# US_EPS_LM.net
KiCad netlist of a schematic drawn in Altium Designer
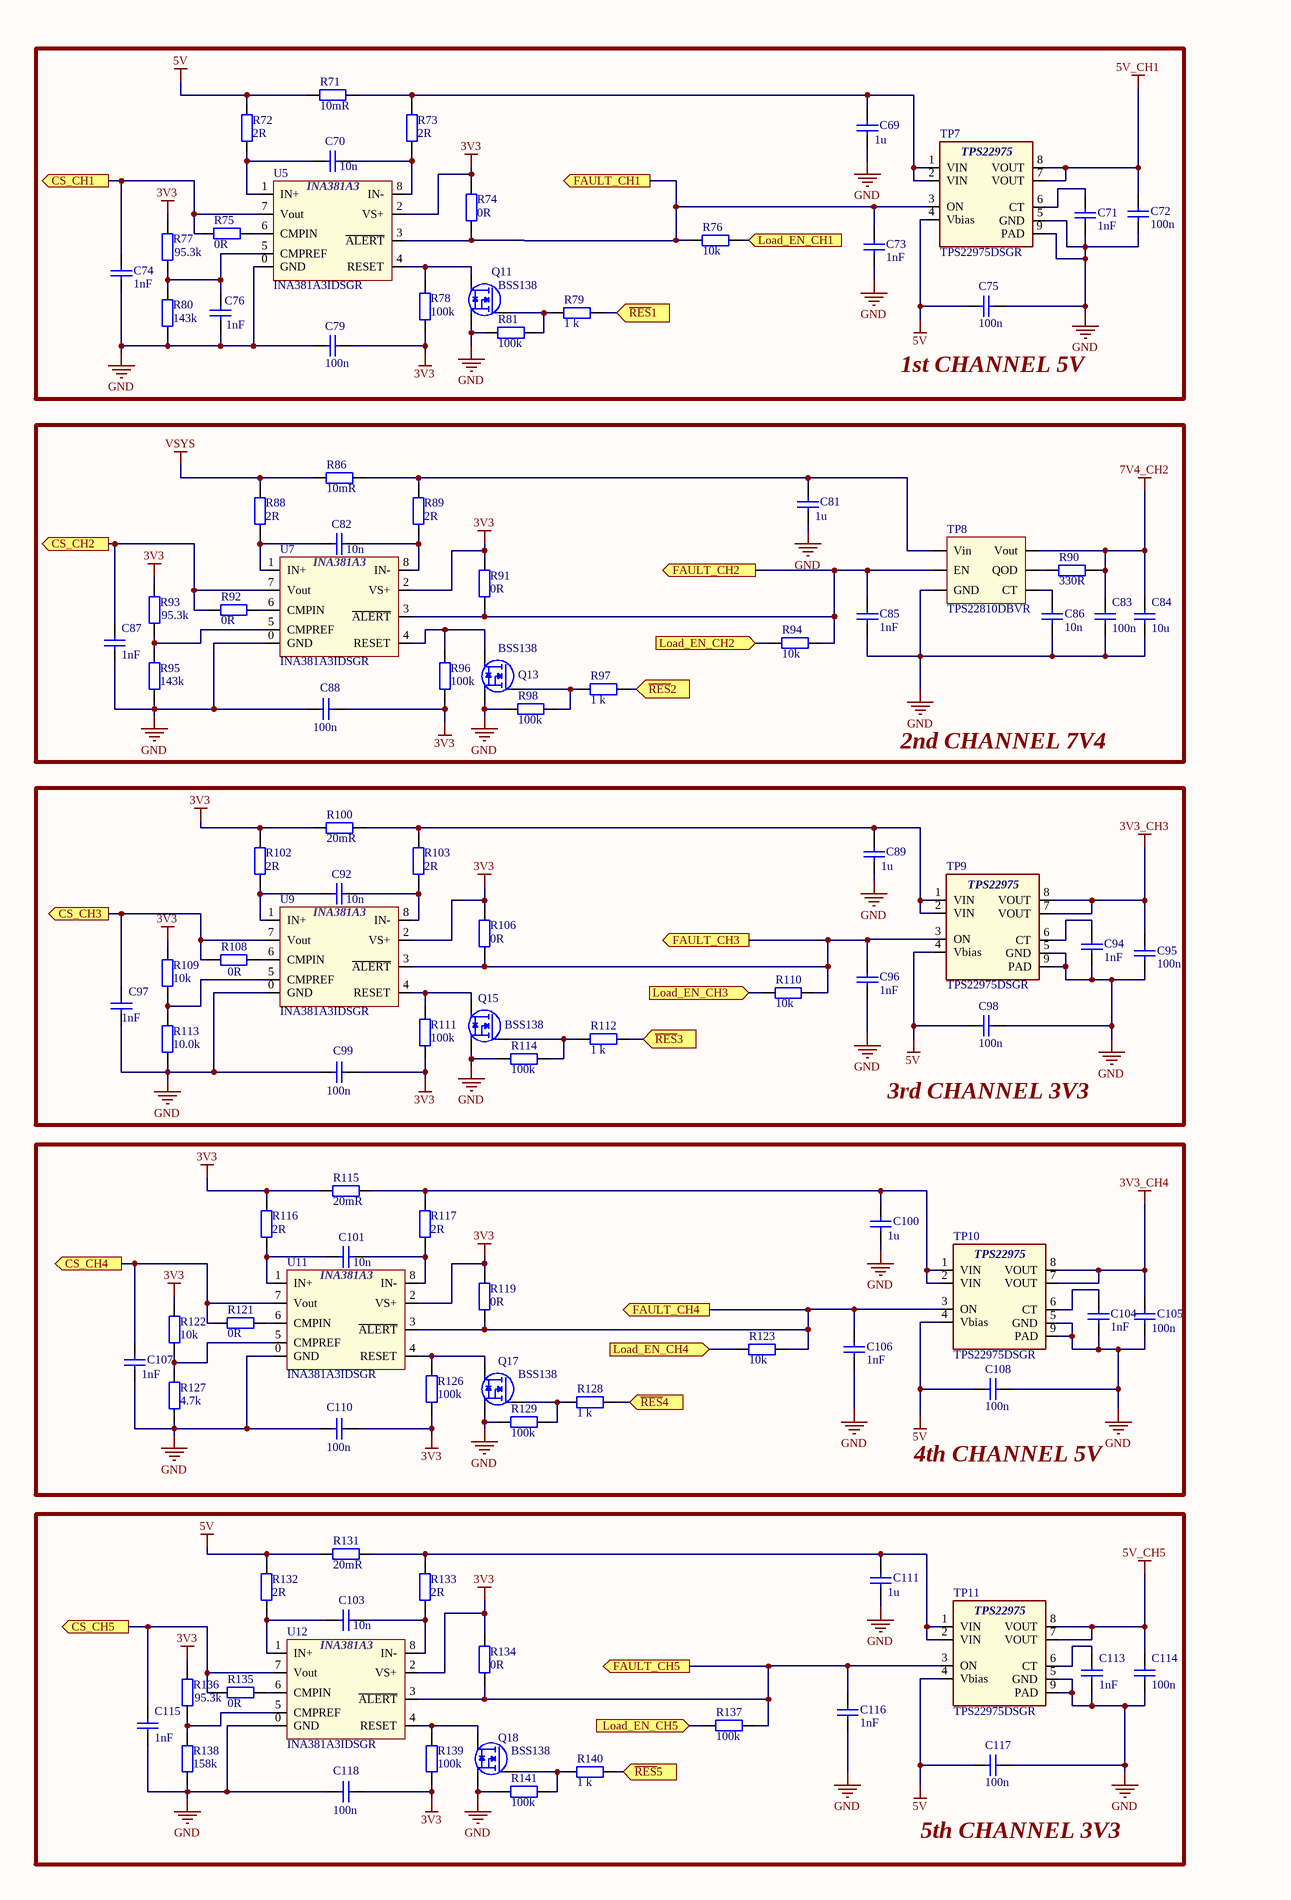
[diagram p0: US_EPS_LM.SchDoc, left]
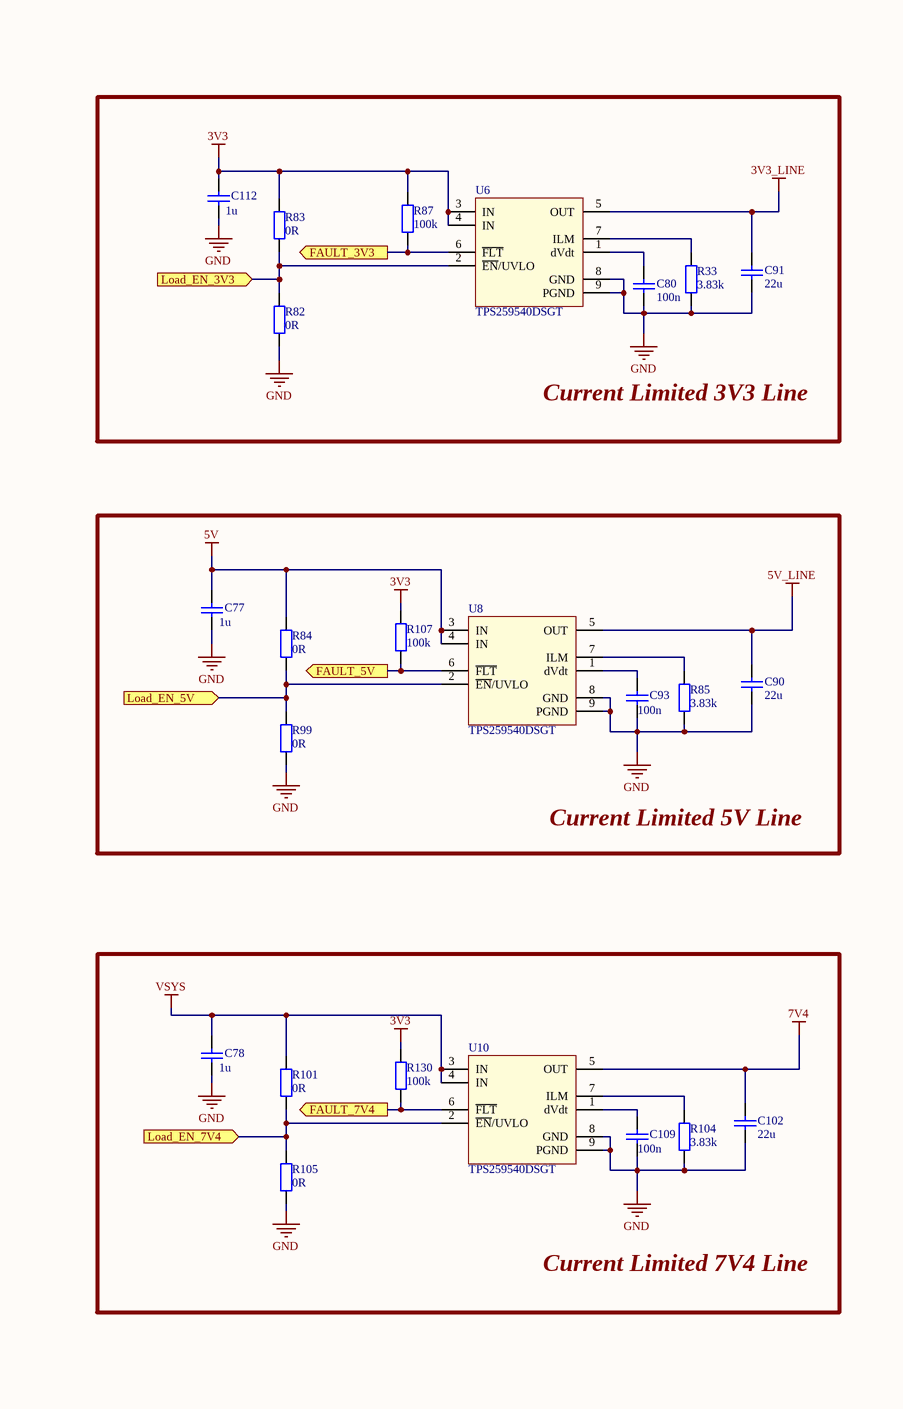
[diagram p1: US_EPS_LM.SchDoc, right]

(export (version "E")
  (design (tool "Eeschema 10.0.6"))
  (components
    (comp (ref "C69")
      (value "1u")
      (footprint "C0603_IPC_HD")
      (description "CAP CER 1UF 16V X7R 0603")
      (fields
        (field (name "MANUFACTURER") "Samsung Electro-Mechanics")
        (field (name "MANUFACTURER PART NUMBER") "CL10B105MO8NNWC")
      )
      (libsource (lib "alfasat_lib") (part "CL10B105MO8NNWC"))
    )
    (comp (ref "C70")
      (value "10n")
      (footprint "C0603_IPC_HD")
      (description "CAP CER 0.01UF 50V X7R 0603")
      (fields
        (field (name "MANUFACTURER") "Samsung Electro-Mechanics")
        (field (name "MANUFACTURER PART NUMBER") "CL10B103KB8NNNC")
      )
      (libsource (lib "alfasat_lib") (part "CL10B103KB8NNNC"))
    )
    (comp (ref "C71")
      (value "1nF")
      (footprint "C0603_IPC_HD")
      (description "CAP CER 1000PF 50V X7R 0603")
      (fields
        (field (name "MANUFACTURER") "Samsung Electro-Mechanics")
        (field (name "MANUFACTURER PART NUMBER") "CL10B102KB8NNNC")
      )
      (libsource (lib "alfasat_lib_eps") (part "CL0603_1nF_0603"))
    )
    (comp (ref "C72")
      (value "100n")
      (footprint "C0603_IPC_HD")
      (description "CAP CER 0.1UF 16V X7R 0603")
      (fields
        (field (name "MANUFACTURER") "Samsung Electro-Mechanics")
        (field (name "MANUFACTURER PART NUMBER") "CL10B104KO8NNNC")
      )
      (libsource (lib "alfasat_lib") (part "CL10B104KO8NNNC"))
    )
    (comp (ref "C73")
      (value "1nF")
      (footprint "C0603_IPC_HD")
      (description "CAP CER 1000PF 50V X7R 0603")
      (fields
        (field (name "MANUFACTURER") "Samsung Electro-Mechanics")
        (field (name "MANUFACTURER PART NUMBER") "CL10B102KB8NNNC")
      )
      (libsource (lib "alfasat_lib_eps") (part "CL0603_1nF_0603"))
    )
    (comp (ref "C74")
      (value "1nF")
      (footprint "C0603_IPC_HD")
      (description "CAP CER 1000PF 50V X7R 0603")
      (fields
        (field (name "MANUFACTURER") "Samsung Electro-Mechanics")
        (field (name "MANUFACTURER PART NUMBER") "CL10B102KB8NNNC")
      )
      (libsource (lib "alfasat_lib_eps") (part "CL0603_1nF_0603"))
    )
    (comp (ref "C75")
      (value "100n")
      (footprint "C0603_IPC_HD")
      (description "CAP CER 0.1UF 16V X7R 0603")
      (fields
        (field (name "MANUFACTURER") "Samsung Electro-Mechanics")
        (field (name "MANUFACTURER PART NUMBER") "CL10B104KO8NNNC")
      )
      (libsource (lib "alfasat_lib") (part "CL10B104KO8NNNC"))
    )
    (comp (ref "C76")
      (value "1nF")
      (footprint "C0603_IPC_HD")
      (description "CAP CER 1000PF 50V X7R 0603")
      (fields
        (field (name "MANUFACTURER") "Samsung Electro-Mechanics")
        (field (name "MANUFACTURER PART NUMBER") "CL10B102KB8NNNC")
      )
      (libsource (lib "alfasat_lib_eps") (part "CL0603_1nF_0603"))
    )
    (comp (ref "C77")
      (value "1u")
      (footprint "C0603_IPC_HD")
      (description "CAP CER 1UF 16V X7R 0603")
      (fields
        (field (name "MANUFACTURER") "Samsung Electro-Mechanics")
        (field (name "MANUFACTURER PART NUMBER") "CL10B105MO8NNWC")
      )
      (libsource (lib "alfasat_parts_lib") (part "CL10B105MO8NNWC"))
    )
    (comp (ref "C78")
      (value "1u")
      (footprint "C0603_IPC_HD")
      (description "CAP CER 1UF 16V X7R 0603")
      (fields
        (field (name "MANUFACTURER") "Samsung Electro-Mechanics")
        (field (name "MANUFACTURER PART NUMBER") "CL10B105MO8NNWC")
      )
      (libsource (lib "alfasat_parts_lib") (part "CL10B105MO8NNWC"))
    )
    (comp (ref "C79")
      (value "100n")
      (footprint "C0603_IPC_HD")
      (description "CAP CER 0.1UF 16V X7R 0603")
      (fields
        (field (name "MANUFACTURER") "Samsung Electro-Mechanics")
        (field (name "MANUFACTURER PART NUMBER") "CL10B104KO8NNNC")
      )
      (libsource (lib "alfasat_lib") (part "CL10B104KO8NNNC"))
    )
    (comp (ref "C80")
      (value "100n")
      (footprint "C0603_IPC_HD")
      (description "CAP CER 0.1UF 16V X7R 0603")
      (fields
        (field (name "MANUFACTURER") "Samsung Electro-Mechanics")
        (field (name "MANUFACTURER PART NUMBER") "CL10B104KO8NNNC")
      )
      (libsource (lib "alfasat_lib") (part "CL10B104KO8NNNC"))
    )
    (comp (ref "C81")
      (value "1u")
      (footprint "C0603_IPC_HD")
      (description "CAP CER 1UF 16V X7R 0603")
      (fields
        (field (name "MANUFACTURER") "Samsung Electro-Mechanics")
        (field (name "MANUFACTURER PART NUMBER") "CL10B105MO8NNWC")
      )
      (libsource (lib "alfasat_lib") (part "CL10B105MO8NNWC"))
    )
    (comp (ref "C82")
      (value "10n")
      (footprint "C0603_IPC_HD")
      (description "CAP CER 0.01UF 50V X7R 0603")
      (fields
        (field (name "MANUFACTURER") "Samsung Electro-Mechanics")
        (field (name "MANUFACTURER PART NUMBER") "CL10B103KB8NNNC")
      )
      (libsource (lib "alfasat_lib") (part "CL10B103KB8NNNC"))
    )
    (comp (ref "C83")
      (value "100n")
      (footprint "C0603_IPC_HD")
      (description "CAP CER 0.1UF 16V X7R 0603")
      (fields
        (field (name "MANUFACTURER") "Samsung Electro-Mechanics")
        (field (name "MANUFACTURER PART NUMBER") "CL10B104KO8NNNC")
      )
      (libsource (lib "alfasat_lib") (part "CL10B104KO8NNNC"))
    )
    (comp (ref "C84")
      (value "10u")
      (footprint "C0805_IPC_HD")
      (description "CAP CER 10UF 16V X7R 0805")
      (fields
        (field (name "MANUFACTURER") "Samsung Electro-Mechanics")
        (field (name "MANUFACTURER PART NUMBER") "CL21B106KOQNNNG")
      )
      (libsource (lib "alfasat_lib") (part "CL21B106KOQNNNG"))
    )
    (comp (ref "C85")
      (value "1nF")
      (footprint "C0603_IPC_HD")
      (description "CAP CER 1000PF 50V X7R 0603")
      (fields
        (field (name "MANUFACTURER") "Samsung Electro-Mechanics")
        (field (name "MANUFACTURER PART NUMBER") "CL10B102KB8NNNC")
      )
      (libsource (lib "alfasat_lib_eps") (part "CL0603_1nF_0603"))
    )
    (comp (ref "C86")
      (value "10n")
      (footprint "C0603_IPC_HD")
      (description "CAP CER 0.01UF 50V X7R 0603")
      (fields
        (field (name "MANUFACTURER") "Samsung Electro-Mechanics")
        (field (name "MANUFACTURER PART NUMBER") "CL10B103KB8NNNC")
      )
      (libsource (lib "alfasat_lib") (part "CL10B103KB8NNNC"))
    )
    (comp (ref "C87")
      (value "1nF")
      (footprint "C0603_IPC_HD")
      (description "CAP CER 1000PF 50V X7R 0603")
      (fields
        (field (name "MANUFACTURER") "Samsung Electro-Mechanics")
        (field (name "MANUFACTURER PART NUMBER") "CL10B102KB8NNNC")
      )
      (libsource (lib "alfasat_lib_eps") (part "CL0603_1nF_0603"))
    )
    (comp (ref "C88")
      (value "100n")
      (footprint "C0603_IPC_HD")
      (description "CAP CER 0.1UF 16V X7R 0603")
      (fields
        (field (name "MANUFACTURER") "Samsung Electro-Mechanics")
        (field (name "MANUFACTURER PART NUMBER") "CL10B104KO8NNNC")
      )
      (libsource (lib "alfasat_lib") (part "CL10B104KO8NNNC"))
    )
    (comp (ref "C89")
      (value "1u")
      (footprint "C0603_IPC_HD")
      (description "CAP CER 1UF 16V X7R 0603")
      (fields
        (field (name "MANUFACTURER") "Samsung Electro-Mechanics")
        (field (name "MANUFACTURER PART NUMBER") "CL10B105MO8NNWC")
      )
      (libsource (lib "alfasat_lib") (part "CL10B105MO8NNWC"))
    )
    (comp (ref "C90")
      (value "22u")
      (footprint "C0805_IPC_HD")
      (description "CAP CER 22UF 16V X5R 0805")
      (fields
        (field (name "MANUFACTURER") "Samsung Electro-Mechanics")
        (field (name "MANUFACTURER PART NUMBER") "CL21A226MOCLRNC")
      )
      (libsource (lib "alfasat_parts_lib") (part "CL21A226MOCLRNC"))
    )
    (comp (ref "C91")
      (value "22u")
      (footprint "C0805_IPC_HD")
      (description "CAP CER 22UF 16V X5R 0805")
      (fields
        (field (name "MANUFACTURER") "Samsung Electro-Mechanics")
        (field (name "MANUFACTURER PART NUMBER") "CL21A226MOCLRNC")
      )
      (libsource (lib "alfasat_parts_lib") (part "CL21A226MOCLRNC"))
    )
    (comp (ref "C92")
      (value "10n")
      (footprint "C0603_IPC_HD")
      (description "CAP CER 0.01UF 50V X7R 0603")
      (fields
        (field (name "MANUFACTURER") "Samsung Electro-Mechanics")
        (field (name "MANUFACTURER PART NUMBER") "CL10B103KB8NNNC")
      )
      (libsource (lib "alfasat_lib") (part "CL10B103KB8NNNC"))
    )
    (comp (ref "C93")
      (value "100n")
      (footprint "C0603_IPC_HD")
      (description "CAP CER 0.1UF 16V X7R 0603")
      (fields
        (field (name "MANUFACTURER") "Samsung Electro-Mechanics")
        (field (name "MANUFACTURER PART NUMBER") "CL10B104KO8NNNC")
      )
      (libsource (lib "alfasat_lib") (part "CL10B104KO8NNNC"))
    )
    (comp (ref "C94")
      (value "1nF")
      (footprint "C0603_IPC_HD")
      (description "CAP CER 1000PF 50V X7R 0603")
      (fields
        (field (name "MANUFACTURER") "Samsung Electro-Mechanics")
        (field (name "MANUFACTURER PART NUMBER") "CL10B102KB8NNNC")
      )
      (libsource (lib "alfasat_lib_eps") (part "CL0603_1nF_0603"))
    )
    (comp (ref "C95")
      (value "100n")
      (footprint "C0603_IPC_HD")
      (description "CAP CER 0.1UF 16V X7R 0603")
      (fields
        (field (name "MANUFACTURER") "Samsung Electro-Mechanics")
        (field (name "MANUFACTURER PART NUMBER") "CL10B104KO8NNNC")
      )
      (libsource (lib "alfasat_lib") (part "CL10B104KO8NNNC"))
    )
    (comp (ref "C96")
      (value "1nF")
      (footprint "C0603_IPC_HD")
      (description "CAP CER 1000PF 50V X7R 0603")
      (fields
        (field (name "MANUFACTURER") "Samsung Electro-Mechanics")
        (field (name "MANUFACTURER PART NUMBER") "CL10B102KB8NNNC")
      )
      (libsource (lib "alfasat_lib_eps") (part "CL0603_1nF_0603"))
    )
    (comp (ref "C97")
      (value "1nF")
      (footprint "C0603_IPC_HD")
      (description "CAP CER 1000PF 50V X7R 0603")
      (fields
        (field (name "MANUFACTURER") "Samsung Electro-Mechanics")
        (field (name "MANUFACTURER PART NUMBER") "CL10B102KB8NNNC")
      )
      (libsource (lib "alfasat_lib_eps") (part "CL0603_1nF_0603"))
    )
    (comp (ref "C98")
      (value "100n")
      (footprint "C0603_IPC_HD")
      (description "CAP CER 0.1UF 16V X7R 0603")
      (fields
        (field (name "MANUFACTURER") "Samsung Electro-Mechanics")
        (field (name "MANUFACTURER PART NUMBER") "CL10B104KO8NNNC")
      )
      (libsource (lib "alfasat_lib") (part "CL10B104KO8NNNC"))
    )
    (comp (ref "C99")
      (value "100n")
      (footprint "C0603_IPC_HD")
      (description "CAP CER 0.1UF 16V X7R 0603")
      (fields
        (field (name "MANUFACTURER") "Samsung Electro-Mechanics")
        (field (name "MANUFACTURER PART NUMBER") "CL10B104KO8NNNC")
      )
      (libsource (lib "alfasat_lib") (part "CL10B104KO8NNNC"))
    )
    (comp (ref "C100")
      (value "1u")
      (footprint "C0603_IPC_HD")
      (description "CAP CER 1UF 16V X7R 0603")
      (fields
        (field (name "MANUFACTURER") "Samsung Electro-Mechanics")
        (field (name "MANUFACTURER PART NUMBER") "CL10B105MO8NNWC")
      )
      (libsource (lib "alfasat_lib") (part "CL10B105MO8NNWC"))
    )
    (comp (ref "C101")
      (value "10n")
      (footprint "C0603_IPC_HD")
      (description "CAP CER 0.01UF 50V X7R 0603")
      (fields
        (field (name "MANUFACTURER") "Samsung Electro-Mechanics")
        (field (name "MANUFACTURER PART NUMBER") "CL10B103KB8NNNC")
      )
      (libsource (lib "alfasat_lib") (part "CL10B103KB8NNNC"))
    )
    (comp (ref "C102")
      (value "22u")
      (footprint "C0805_IPC_HD")
      (description "CAP CER 22UF 16V X5R 0805")
      (fields
        (field (name "MANUFACTURER") "Samsung Electro-Mechanics")
        (field (name "MANUFACTURER PART NUMBER") "CL21A226MOCLRNC")
      )
      (libsource (lib "alfasat_lib") (part "CL21A226MOCLRNC"))
    )
    (comp (ref "C103")
      (value "10n")
      (footprint "C0603_IPC_HD")
      (description "CAP CER 0.01UF 50V X7R 0603")
      (fields
        (field (name "MANUFACTURER") "Samsung Electro-Mechanics")
        (field (name "MANUFACTURER PART NUMBER") "CL10B103KB8NNNC")
      )
      (libsource (lib "alfasat_lib") (part "CL10B103KB8NNNC"))
    )
    (comp (ref "C104")
      (value "1nF")
      (footprint "C0603_IPC_HD")
      (description "CAP CER 1000PF 50V X7R 0603")
      (fields
        (field (name "MANUFACTURER") "Samsung Electro-Mechanics")
        (field (name "MANUFACTURER PART NUMBER") "CL10B102KB8NNNC")
      )
      (libsource (lib "alfasat_lib_eps") (part "CL0603_1nF_0603"))
    )
    (comp (ref "C105")
      (value "100n")
      (footprint "C0603_IPC_HD")
      (description "CAP CER 0.1UF 16V X7R 0603")
      (fields
        (field (name "MANUFACTURER") "Samsung Electro-Mechanics")
        (field (name "MANUFACTURER PART NUMBER") "CL10B104KO8NNNC")
      )
      (libsource (lib "alfasat_lib") (part "CL10B104KO8NNNC"))
    )
    (comp (ref "C106")
      (value "1nF")
      (footprint "C0603_IPC_HD")
      (description "CAP CER 1000PF 50V X7R 0603")
      (fields
        (field (name "MANUFACTURER") "Samsung Electro-Mechanics")
        (field (name "MANUFACTURER PART NUMBER") "CL10B102KB8NNNC")
      )
      (libsource (lib "alfasat_lib_eps") (part "CL0603_1nF_0603"))
    )
    (comp (ref "C107")
      (value "1nF")
      (footprint "C0603_IPC_HD")
      (description "CAP CER 1000PF 50V X7R 0603")
      (fields
        (field (name "MANUFACTURER") "Samsung Electro-Mechanics")
        (field (name "MANUFACTURER PART NUMBER") "CL10B102KB8NNNC")
      )
      (libsource (lib "alfasat_lib_eps") (part "CL0603_1nF_0603"))
    )
    (comp (ref "C108")
      (value "100n")
      (footprint "C0603_IPC_HD")
      (description "CAP CER 0.1UF 16V X7R 0603")
      (fields
        (field (name "MANUFACTURER") "Samsung Electro-Mechanics")
        (field (name "MANUFACTURER PART NUMBER") "CL10B104KO8NNNC")
      )
      (libsource (lib "alfasat_lib") (part "CL10B104KO8NNNC"))
    )
    (comp (ref "C109")
      (value "100n")
      (footprint "C0603_IPC_HD")
      (description "CAP CER 0.1UF 16V X7R 0603")
      (fields
        (field (name "MANUFACTURER") "Samsung Electro-Mechanics")
        (field (name "MANUFACTURER PART NUMBER") "CL10B104KO8NNNC")
      )
      (libsource (lib "alfasat_lib") (part "CL10B104KO8NNNC"))
    )
    (comp (ref "C110")
      (value "100n")
      (footprint "C0603_IPC_HD")
      (description "CAP CER 0.1UF 16V X7R 0603")
      (fields
        (field (name "MANUFACTURER") "Samsung Electro-Mechanics")
        (field (name "MANUFACTURER PART NUMBER") "CL10B104KO8NNNC")
      )
      (libsource (lib "alfasat_lib") (part "CL10B104KO8NNNC"))
    )
    (comp (ref "C111")
      (value "1u")
      (footprint "C0603_IPC_HD")
      (description "CAP CER 1UF 16V X7R 0603")
      (fields
        (field (name "MANUFACTURER") "Samsung Electro-Mechanics")
        (field (name "MANUFACTURER PART NUMBER") "CL10B105MO8NNWC")
      )
      (libsource (lib "alfasat_lib") (part "CL10B105MO8NNWC"))
    )
    (comp (ref "C112")
      (value "1u")
      (footprint "C0603_IPC_HD")
      (description "CAP CER 1UF 16V X7R 0603")
      (fields
        (field (name "MANUFACTURER") "Samsung Electro-Mechanics")
        (field (name "MANUFACTURER PART NUMBER") "CL10B105MO8NNWC")
      )
      (libsource (lib "alfasat_parts_lib") (part "CL10B105MO8NNWC"))
    )
    (comp (ref "C113")
      (value "1nF")
      (footprint "C0603_IPC_HD")
      (description "CAP CER 1000PF 50V X7R 0603")
      (fields
        (field (name "MANUFACTURER") "Samsung Electro-Mechanics")
        (field (name "MANUFACTURER PART NUMBER") "CL10B102KB8NNNC")
      )
      (libsource (lib "alfasat_lib_eps") (part "CL0603_1nF_0603"))
    )
    (comp (ref "C114")
      (value "100n")
      (footprint "C0603_IPC_HD")
      (description "CAP CER 0.1UF 16V X7R 0603")
      (fields
        (field (name "MANUFACTURER") "Samsung Electro-Mechanics")
        (field (name "MANUFACTURER PART NUMBER") "CL10B104KO8NNNC")
      )
      (libsource (lib "alfasat_lib") (part "CL10B104KO8NNNC"))
    )
    (comp (ref "C115")
      (value "1nF")
      (footprint "C0603_IPC_HD")
      (description "CAP CER 1000PF 50V X7R 0603")
      (fields
        (field (name "MANUFACTURER") "Samsung Electro-Mechanics")
        (field (name "MANUFACTURER PART NUMBER") "CL10B102KB8NNNC")
      )
      (libsource (lib "alfasat_lib_eps") (part "CL0603_1nF_0603"))
    )
    (comp (ref "C116")
      (value "1nF")
      (footprint "C0603_IPC_HD")
      (description "CAP CER 1000PF 50V X7R 0603")
      (fields
        (field (name "MANUFACTURER") "Samsung Electro-Mechanics")
        (field (name "MANUFACTURER PART NUMBER") "CL10B102KB8NNNC")
      )
      (libsource (lib "alfasat_lib_eps") (part "CL0603_1nF_0603"))
    )
    (comp (ref "C117")
      (value "100n")
      (footprint "C0603_IPC_HD")
      (description "CAP CER 0.1UF 16V X7R 0603")
      (fields
        (field (name "MANUFACTURER") "Samsung Electro-Mechanics")
        (field (name "MANUFACTURER PART NUMBER") "CL10B104KO8NNNC")
      )
      (libsource (lib "alfasat_lib") (part "CL10B104KO8NNNC"))
    )
    (comp (ref "C118")
      (value "100n")
      (footprint "C0603_IPC_HD")
      (description "CAP CER 0.1UF 16V X7R 0603")
      (fields
        (field (name "MANUFACTURER") "Samsung Electro-Mechanics")
        (field (name "MANUFACTURER PART NUMBER") "CL10B104KO8NNNC")
      )
      (libsource (lib "alfasat_lib") (part "CL10B104KO8NNNC"))
    )
    (comp (ref "Q11")
      (value "BSS138")
      (footprint "SOT23")
      (description "N-Channel Logic Level Enhancement Mode Field Effect Transistor")
      (fields (field (name "MANUFACTURER") "Diodes Incorporated"))
      (libsource (lib "alfasat_lib") (part "BSS138"))
    )
    (comp (ref "Q13")
      (value "BSS138")
      (footprint "SOT23")
      (description "N-Channel Logic Level Enhancement Mode Field Effect Transistor")
      (fields (field (name "MANUFACTURER") "Diodes Incorporated"))
      (libsource (lib "alfasat_lib") (part "BSS138"))
    )
    (comp (ref "Q15")
      (value "BSS138")
      (footprint "SOT23")
      (description "N-Channel Logic Level Enhancement Mode Field Effect Transistor")
      (fields (field (name "MANUFACTURER") "Diodes Incorporated"))
      (libsource (lib "alfasat_lib") (part "BSS138"))
    )
    (comp (ref "Q17")
      (value "BSS138")
      (footprint "SOT23")
      (description "N-Channel Logic Level Enhancement Mode Field Effect Transistor")
      (fields (field (name "MANUFACTURER") "Diodes Incorporated"))
      (libsource (lib "alfasat_lib") (part "BSS138"))
    )
    (comp (ref "Q18")
      (value "BSS138")
      (footprint "SOT23")
      (description "N-Channel Logic Level Enhancement Mode Field Effect Transistor")
      (fields (field (name "MANUFACTURER") "Diodes Incorporated"))
      (libsource (lib "alfasat_lib") (part "BSS138"))
    )
    (comp (ref "R33")
      (value "3.83k")
      (footprint "C0603_IPC_HD")
      (description "RES SMD 3.83K OHM 1% 1/10W 0603")
      (fields
        (field (name "MANUFACTURER") "Yageo")
        (field (name "MANUFACTURER PART NUMBER") "RC0603FR-073K83L")
      )
      (libsource (lib "alfasat_lib_eps") (part "CR0603-JW-3.83k"))
    )
    (comp (ref "R71")
      (value "10mR")
      (footprint "WSLP1206R001")
      (fields
        (field (name "MANUFACTURER") "Vishay Dale")
        (field (name "MANUFACTURER PART NUMBER") "WSLP1206R0100FEA")
      )
      (libsource (lib "alfasat_lib_eps") (part "WSLP1206R001"))
    )
    (comp (ref "R72")
      (value "2R")
      (footprint "alfasat_lib_eps:C0603_IPC_HD")
      (description "2 Ohms ±1% 0.125W, 1/8W Chip Resistor 0603 (1608 Metric) Automotive AEC-Q200 Thick Film")
      (fields
        (field (name "MANUFACTURER") "KOA Speer Electronics, Inc.")
        (field (name "MANUFACTURER PART NUMBER") "RK73H1JTTD2R00F")
      )
      (libsource (lib "alfasat_lib_eps") (part "CR0603-JW-2R"))
    )
    (comp (ref "R73")
      (value "2R")
      (footprint "alfasat_lib_eps:C0603_IPC_HD")
      (description "2 Ohms ±1% 0.125W, 1/8W Chip Resistor 0603 (1608 Metric) Automotive AEC-Q200 Thick Film")
      (fields
        (field (name "MANUFACTURER") "KOA Speer Electronics, Inc.")
        (field (name "MANUFACTURER PART NUMBER") "RK73H1JTTD2R00F")
      )
      (libsource (lib "alfasat_lib_eps") (part "CR0603-JW-2R"))
    )
    (comp (ref "R74")
      (value "0R")
      (footprint "R0603_IPC_MD")
      (description "RES SMD 0 OHM JUMPER 1/10W 0603")
      (fields
        (field (name "MANUFACTURER") "Bourns Inc.")
        (field (name "MANUFACTURER PART NUMBER") "CR0603-J/-000ELF")
      )
      (libsource (lib "alfasat_lib") (part "CR0603-J/-000ELF"))
    )
    (comp (ref "R75")
      (value "0R")
      (footprint "R0603_IPC_MD")
      (description "RES SMD 0 OHM JUMPER 1/10W 0603")
      (fields
        (field (name "MANUFACTURER") "Bourns Inc.")
        (field (name "MANUFACTURER PART NUMBER") "CR0603-J/-000ELF")
      )
      (libsource (lib "") (part "CR0603-J/-000ELF_1"))
    )
    (comp (ref "R76")
      (value "10k")
      (footprint "C0603_IPC_HD")
      (description "RES 10K OHM 1% 1/10W 0603")
      (fields
        (field (name "MANUFACTURER") "Stackpole Electronics Inc")
        (field (name "MANUFACTURER PART NUMBER") "RMCF0603FT10K0")
      )
      (libsource (lib "") (part "CR0603-JW-10k_1"))
    )
    (comp (ref "R77")
      (value "95.3k")
      (footprint "C0603_IPC_HD")
      (description "RES 95.3K OHM 1% 1/10W 0603")
      (fields
        (field (name "MANUFACTURER") "Stackpole Electronics Inc")
        (field (name "MANUFACTURER PART NUMBER") "RMCF0603FT95K3")
      )
      (libsource (lib "alfasat_lib_eps") (part "CR0603-JW-95.3k"))
    )
    (comp (ref "R78")
      (value "100k")
      (footprint "R0603_IPC_MD")
      (description "RES 100K OHM 1% 1/10W 0603")
      (fields
        (field (name "MANUFACTURER") "Stackpole Electronics Inc")
        (field (name "MANUFACTURER PART NUMBER") "RMCF0603FT100K")
      )
      (libsource (lib "") (part "CR0603-JW-104ELF_1"))
    )
    (comp (ref "R79")
      (value "1 k")
      (footprint "R0603_IPC_HD")
      (description "1 kOhms ±1% 0.1W, 1/10W Chip Resistor 0603 (1608 Metric) Automotive AEC-Q200 Thick Film")
      (fields
        (field (name "MANUFACTURER") "Stackpole Electronics Inc")
        (field (name "MANUFACTURER PART NUMBER") "RMCF0603FT1K00")
      )
      (libsource (lib "alfasat_lib_eps") (part "CR0603-JW-1k_ISL92"))
    )
    (comp (ref "R80")
      (value "143k")
      (footprint "alfasat_lib_eps:C0603_IPC_HD")
      (description "RES 143K OHM 1% 1/10W 0603")
      (fields
        (field (name "MANUFACTURER") "Stackpole Electronics Inc")
        (field (name "MANUFACTURER PART NUMBER") "RMCF0603FT143K")
      )
      (libsource (lib "alfasat_lib_eps") (part "CR0603-JW-147kR"))
    )
    (comp (ref "R81")
      (value "100k")
      (footprint "R0603_IPC_MD")
      (description "RES 100K OHM 1% 1/10W 0603")
      (fields
        (field (name "MANUFACTURER") "Stackpole Electronics Inc")
        (field (name "MANUFACTURER PART NUMBER") "RMCF0603FT100K")
      )
      (libsource (lib "") (part "CR0603-JW-104ELF_3"))
    )
    (comp (ref "R82")
      (value "0R")
      (footprint "R0603_IPC_MD")
      (description "RES SMD 0 OHM JUMPER 1/10W 0603")
      (fields
        (field (name "MANUFACTURER") "Bourns Inc.")
        (field (name "MANUFACTURER PART NUMBER") "CR0603-J/-000ELF")
      )
      (libsource (lib "") (part "CR0603-J/-000ELF_3"))
    )
    (comp (ref "R83")
      (value "0R")
      (footprint "R0603_IPC_MD")
      (description "RES SMD 0 OHM JUMPER 1/10W 0603")
      (fields
        (field (name "MANUFACTURER") "Bourns Inc.")
        (field (name "MANUFACTURER PART NUMBER") "CR0603-J/-000ELF")
      )
      (libsource (lib "") (part "CR0603-J/-000ELF_3"))
    )
    (comp (ref "R84")
      (value "0R")
      (footprint "R0603_IPC_MD")
      (description "RES SMD 0 OHM JUMPER 1/10W 0603")
      (fields
        (field (name "MANUFACTURER") "Bourns Inc.")
        (field (name "MANUFACTURER PART NUMBER") "CR0603-J/-000ELF")
      )
      (libsource (lib "alfasat_parts_lib") (part "CR0603-J/-000ELF"))
    )
    (comp (ref "R85")
      (value "3.83k")
      (footprint "C0603_IPC_HD")
      (description "RES SMD 3.83K OHM 1% 1/10W 0603")
      (fields
        (field (name "MANUFACTURER") "Yageo")
        (field (name "MANUFACTURER PART NUMBER") "RC0603FR-073K83L")
      )
      (libsource (lib "alfasat_lib_eps") (part "CR0603-JW-3.83k"))
    )
    (comp (ref "R86")
      (value "10mR")
      (footprint "WSLP1206R001")
      (fields
        (field (name "MANUFACTURER") "Vishay Dale")
        (field (name "MANUFACTURER PART NUMBER") "WSLP1206R0100FEA")
      )
      (libsource (lib "alfasat_lib_eps") (part "WSLP1206R001"))
    )
    (comp (ref "R87")
      (value "100k")
      (footprint "R0603_IPC_MD")
      (description "RES 100K OHM 1% 1/10W 0603")
      (fields
        (field (name "MANUFACTURER") "Stackpole Electronics Inc")
        (field (name "MANUFACTURER PART NUMBER") "RMCF0603FT100K")
      )
      (libsource (lib "") (part "CR0603-JW-104ELF_1"))
    )
    (comp (ref "R88")
      (value "2R")
      (footprint "alfasat_lib_eps:C0603_IPC_HD")
      (description "2 Ohms ±1% 0.125W, 1/8W Chip Resistor 0603 (1608 Metric) Automotive AEC-Q200 Thick Film")
      (fields
        (field (name "MANUFACTURER") "KOA Speer Electronics, Inc.")
        (field (name "MANUFACTURER PART NUMBER") "RK73H1JTTD2R00F")
      )
      (libsource (lib "alfasat_lib_eps") (part "CR0603-JW-2R"))
    )
    (comp (ref "R89")
      (value "2R")
      (footprint "alfasat_lib_eps:C0603_IPC_HD")
      (description "2 Ohms ±1% 0.125W, 1/8W Chip Resistor 0603 (1608 Metric) Automotive AEC-Q200 Thick Film")
      (fields
        (field (name "MANUFACTURER") "KOA Speer Electronics, Inc.")
        (field (name "MANUFACTURER PART NUMBER") "RK73H1JTTD2R00F")
      )
      (libsource (lib "alfasat_lib_eps") (part "CR0603-JW-2R"))
    )
    (comp (ref "R90")
      (value "330R")
      (footprint "R0603_IPC_MD")
      (description "RES SMD 330 OHM 5% 1/10W 0603")
      (fields
        (field (name "MANUFACTURER") "Bourns Inc.")
        (field (name "MANUFACTURER PART NUMBER") "CR0603-JW-331ELF")
      )
      (libsource (lib "alfasat_lib") (part "CR0603-JW-331ELF"))
    )
    (comp (ref "R91")
      (value "0R")
      (footprint "R0603_IPC_MD")
      (description "RES SMD 0 OHM JUMPER 1/10W 0603")
      (fields
        (field (name "MANUFACTURER") "Bourns Inc.")
        (field (name "MANUFACTURER PART NUMBER") "CR0603-J/-000ELF")
      )
      (libsource (lib "alfasat_lib") (part "CR0603-J/-000ELF"))
    )
    (comp (ref "R92")
      (value "0R")
      (footprint "R0603_IPC_MD")
      (description "RES SMD 0 OHM JUMPER 1/10W 0603")
      (fields
        (field (name "MANUFACTURER") "Bourns Inc.")
        (field (name "MANUFACTURER PART NUMBER") "CR0603-J/-000ELF")
      )
      (libsource (lib "") (part "CR0603-J/-000ELF_1"))
    )
    (comp (ref "R93")
      (value "95.3k")
      (footprint "C0603_IPC_HD")
      (description "RES 95.3K OHM 1% 1/10W 0603")
      (fields
        (field (name "MANUFACTURER") "Stackpole Electronics Inc")
        (field (name "MANUFACTURER PART NUMBER") "RMCF0603FT95K3")
      )
      (libsource (lib "alfasat_lib_eps") (part "CR0603-JW-95.3k"))
    )
    (comp (ref "R94")
      (value "10k")
      (footprint "C0603_IPC_HD")
      (description "RES 10K OHM 1% 1/10W 0603")
      (fields
        (field (name "MANUFACTURER") "Stackpole Electronics Inc")
        (field (name "MANUFACTURER PART NUMBER") "RMCF0603FT10K0")
      )
      (libsource (lib "") (part "CR0603-JW-10k_1"))
    )
    (comp (ref "R95")
      (value "143k")
      (footprint "alfasat_lib_eps:C0603_IPC_HD")
      (description "RES 143K OHM 1% 1/10W 0603")
      (fields
        (field (name "MANUFACTURER") "Stackpole Electronics Inc")
        (field (name "MANUFACTURER PART NUMBER") "RMCF0603FT143K")
      )
      (libsource (lib "alfasat_lib_eps") (part "CR0603-JW-147kR"))
    )
    (comp (ref "R96")
      (value "100k")
      (footprint "R0603_IPC_MD")
      (description "RES 100K OHM 1% 1/10W 0603")
      (fields
        (field (name "MANUFACTURER") "Stackpole Electronics Inc")
        (field (name "MANUFACTURER PART NUMBER") "RMCF0603FT100K")
      )
      (libsource (lib "") (part "CR0603-JW-104ELF_2"))
    )
    (comp (ref "R97")
      (value "1 k")
      (footprint "R0603_IPC_HD")
      (description "1 kOhms ±1% 0.1W, 1/10W Chip Resistor 0603 (1608 Metric) Automotive AEC-Q200 Thick Film")
      (fields
        (field (name "MANUFACTURER") "Stackpole Electronics Inc")
        (field (name "MANUFACTURER PART NUMBER") "RMCF0603FT1K00")
      )
      (libsource (lib "alfasat_lib_eps") (part "CR0603-JW-1k_ISL92"))
    )
    (comp (ref "R98")
      (value "100k")
      (footprint "R0603_IPC_MD")
      (description "RES 100K OHM 1% 1/10W 0603")
      (fields
        (field (name "MANUFACTURER") "Stackpole Electronics Inc")
        (field (name "MANUFACTURER PART NUMBER") "RMCF0603FT100K")
      )
      (libsource (lib "alfasat_lib_eps") (part "CR0603-JW-104ELF"))
    )
    (comp (ref "R99")
      (value "0R")
      (footprint "R0603_IPC_MD")
      (description "RES SMD 0 OHM JUMPER 1/10W 0603")
      (fields
        (field (name "MANUFACTURER") "Bourns Inc.")
        (field (name "MANUFACTURER PART NUMBER") "CR0603-J/-000ELF")
      )
      (libsource (lib "") (part "CR0603-J/-000ELF_3"))
    )
    (comp (ref "R100")
      (value "20mR")
      (footprint "alfasat_lib_eps:WSLP1206R002")
      (fields
        (field (name "MANUFACTURER") "Vishay Dale")
        (field (name "MANUFACTURER PART NUMBER") "WSLP1206R0200FEA")
      )
      (libsource (lib "alfasat_lib_eps") (part "WSLP1206R002"))
    )
    (comp (ref "R101")
      (value "0R")
      (footprint "R0603_IPC_MD")
      (description "RES SMD 0 OHM JUMPER 1/10W 0603")
      (fields
        (field (name "MANUFACTURER") "Bourns Inc.")
        (field (name "MANUFACTURER PART NUMBER") "CR0603-J/-000ELF")
      )
      (libsource (lib "") (part "CR0603-J/-000ELF_3"))
    )
    (comp (ref "R102")
      (value "2R")
      (footprint "alfasat_lib_eps:C0603_IPC_HD")
      (description "2 Ohms ±1% 0.125W, 1/8W Chip Resistor 0603 (1608 Metric) Automotive AEC-Q200 Thick Film")
      (fields
        (field (name "MANUFACTURER") "KOA Speer Electronics, Inc.")
        (field (name "MANUFACTURER PART NUMBER") "RK73H1JTTD2R00F")
      )
      (libsource (lib "alfasat_lib_eps") (part "CR0603-JW-2R"))
    )
    (comp (ref "R103")
      (value "2R")
      (footprint "alfasat_lib_eps:C0603_IPC_HD")
      (description "2 Ohms ±1% 0.125W, 1/8W Chip Resistor 0603 (1608 Metric) Automotive AEC-Q200 Thick Film")
      (fields
        (field (name "MANUFACTURER") "KOA Speer Electronics, Inc.")
        (field (name "MANUFACTURER PART NUMBER") "RK73H1JTTD2R00F")
      )
      (libsource (lib "alfasat_lib_eps") (part "CR0603-JW-2R"))
    )
    (comp (ref "R104")
      (value "3.83k")
      (footprint "C0603_IPC_HD")
      (description "RES SMD 3.83K OHM 1% 1/10W 0603")
      (fields
        (field (name "MANUFACTURER") "Yageo")
        (field (name "MANUFACTURER PART NUMBER") "RC0603FR-073K83L")
      )
      (libsource (lib "alfasat_lib_eps") (part "CR0603-JW-3.83k"))
    )
    (comp (ref "R105")
      (value "0R")
      (footprint "R0603_IPC_MD")
      (description "RES SMD 0 OHM JUMPER 1/10W 0603")
      (fields
        (field (name "MANUFACTURER") "Bourns Inc.")
        (field (name "MANUFACTURER PART NUMBER") "CR0603-J/-000ELF")
      )
      (libsource (lib "") (part "CR0603-J/-000ELF_3"))
    )
    (comp (ref "R106")
      (value "0R")
      (footprint "R0603_IPC_MD")
      (description "RES SMD 0 OHM JUMPER 1/10W 0603")
      (fields
        (field (name "MANUFACTURER") "Bourns Inc.")
        (field (name "MANUFACTURER PART NUMBER") "CR0603-J/-000ELF")
      )
      (libsource (lib "alfasat_lib") (part "CR0603-J/-000ELF"))
    )
    (comp (ref "R107")
      (value "100k")
      (footprint "R0603_IPC_MD")
      (description "RES 100K OHM 1% 1/10W 0603")
      (fields
        (field (name "MANUFACTURER") "Stackpole Electronics Inc")
        (field (name "MANUFACTURER PART NUMBER") "RMCF0603FT100K")
      )
      (libsource (lib "") (part "CR0603-JW-104ELF_1"))
    )
    (comp (ref "R108")
      (value "0R")
      (footprint "R0603_IPC_MD")
      (description "RES SMD 0 OHM JUMPER 1/10W 0603")
      (fields
        (field (name "MANUFACTURER") "Bourns Inc.")
        (field (name "MANUFACTURER PART NUMBER") "CR0603-J/-000ELF")
      )
      (libsource (lib "") (part "CR0603-J/-000ELF_2"))
    )
    (comp (ref "R109")
      (value "10k")
      (footprint "C0603_IPC_HD")
      (description "RES 10K OHM 1% 1/10W 0603")
      (fields
        (field (name "MANUFACTURER") "Stackpole Electronics Inc")
        (field (name "MANUFACTURER PART NUMBER") "RMCF0603FT10K0")
      )
      (libsource (lib "alfasat_lib_eps") (part "CR0603-JW-10k"))
    )
    (comp (ref "R110")
      (value "10k")
      (footprint "C0603_IPC_HD")
      (description "RES 10K OHM 1% 1/10W 0603")
      (fields
        (field (name "MANUFACTURER") "Stackpole Electronics Inc")
        (field (name "MANUFACTURER PART NUMBER") "RMCF0603FT10K0")
      )
      (libsource (lib "") (part "CR0603-JW-10k_1"))
    )
    (comp (ref "R111")
      (value "100k")
      (footprint "R0603_IPC_MD")
      (description "RES 100K OHM 1% 1/10W 0603")
      (fields
        (field (name "MANUFACTURER") "Stackpole Electronics Inc")
        (field (name "MANUFACTURER PART NUMBER") "RMCF0603FT100K")
      )
      (libsource (lib "") (part "CR0603-JW-104ELF_2"))
    )
    (comp (ref "R112")
      (value "1 k")
      (footprint "R0603_IPC_HD")
      (description "1 kOhms ±1% 0.1W, 1/10W Chip Resistor 0603 (1608 Metric) Automotive AEC-Q200 Thick Film")
      (fields
        (field (name "MANUFACTURER") "Stackpole Electronics Inc")
        (field (name "MANUFACTURER PART NUMBER") "RMCF0603FT1K00")
      )
      (libsource (lib "alfasat_lib_eps") (part "CR0603-JW-1k_ISL92"))
    )
    (comp (ref "R113")
      (value "10.0k")
      (footprint "R0603_IPC_MD")
      (description "RES 10K OHM 1% 1/10W 0603")
      (fields
        (field (name "MANUFACTURER") "Stackpole Electronics Inc")
        (field (name "MANUFACTURER PART NUMBER") "RMCF0603FT10K0")
      )
      (libsource (lib "alfasat_parts_lib") (part "RMCF0603FT10K0"))
    )
    (comp (ref "R114")
      (value "100k")
      (footprint "R0603_IPC_MD")
      (description "RES 100K OHM 1% 1/10W 0603")
      (fields
        (field (name "MANUFACTURER") "Stackpole Electronics Inc")
        (field (name "MANUFACTURER PART NUMBER") "RMCF0603FT100K")
      )
      (libsource (lib "alfasat_lib_eps") (part "CR0603-JW-104ELF"))
    )
    (comp (ref "R115")
      (value "20mR")
      (footprint "alfasat_lib_eps:WSLP1206R002")
      (fields
        (field (name "MANUFACTURER") "Vishay Dale")
        (field (name "MANUFACTURER PART NUMBER") "WSLP1206R0200FEA")
      )
      (libsource (lib "alfasat_lib_eps") (part "WSLP1206R002"))
    )
    (comp (ref "R116")
      (value "2R")
      (footprint "alfasat_lib_eps:C0603_IPC_HD")
      (description "2 Ohms ±1% 0.125W, 1/8W Chip Resistor 0603 (1608 Metric) Automotive AEC-Q200 Thick Film")
      (fields
        (field (name "MANUFACTURER") "KOA Speer Electronics, Inc.")
        (field (name "MANUFACTURER PART NUMBER") "RK73H1JTTD2R00F")
      )
      (libsource (lib "alfasat_lib_eps") (part "CR0603-JW-2R"))
    )
    (comp (ref "R117")
      (value "2R")
      (footprint "alfasat_lib_eps:C0603_IPC_HD")
      (description "2 Ohms ±1% 0.125W, 1/8W Chip Resistor 0603 (1608 Metric) Automotive AEC-Q200 Thick Film")
      (fields
        (field (name "MANUFACTURER") "KOA Speer Electronics, Inc.")
        (field (name "MANUFACTURER PART NUMBER") "RK73H1JTTD2R00F")
      )
      (libsource (lib "alfasat_lib_eps") (part "CR0603-JW-2R"))
    )
    (comp (ref "R119")
      (value "0R")
      (footprint "R0603_IPC_MD")
      (description "RES SMD 0 OHM JUMPER 1/10W 0603")
      (fields
        (field (name "MANUFACTURER") "Bourns Inc.")
        (field (name "MANUFACTURER PART NUMBER") "CR0603-J/-000ELF")
      )
      (libsource (lib "alfasat_lib") (part "CR0603-J/-000ELF"))
    )
    (comp (ref "R121")
      (value "0R")
      (footprint "R0603_IPC_MD")
      (description "RES SMD 0 OHM JUMPER 1/10W 0603")
      (fields
        (field (name "MANUFACTURER") "Bourns Inc.")
        (field (name "MANUFACTURER PART NUMBER") "CR0603-J/-000ELF")
      )
      (libsource (lib "") (part "CR0603-J/-000ELF_2"))
    )
    (comp (ref "R122")
      (value "10k")
      (footprint "C0603_IPC_HD")
      (description "RES 10K OHM 1% 1/10W 0603")
      (fields
        (field (name "MANUFACTURER") "Stackpole Electronics Inc")
        (field (name "MANUFACTURER PART NUMBER") "RMCF0603FT10K0")
      )
      (libsource (lib "alfasat_lib_eps") (part "CR0603-JW-10k"))
    )
    (comp (ref "R123")
      (value "10k")
      (footprint "C0603_IPC_HD")
      (description "RES 10K OHM 1% 1/10W 0603")
      (fields
        (field (name "MANUFACTURER") "Stackpole Electronics Inc")
        (field (name "MANUFACTURER PART NUMBER") "RMCF0603FT10K0")
      )
      (libsource (lib "") (part "CR0603-JW-10k_1"))
    )
    (comp (ref "R126")
      (value "100k")
      (footprint "R0603_IPC_MD")
      (description "RES 100K OHM 1% 1/10W 0603")
      (fields
        (field (name "MANUFACTURER") "Stackpole Electronics Inc")
        (field (name "MANUFACTURER PART NUMBER") "RMCF0603FT100K")
      )
      (libsource (lib "") (part "CR0603-JW-104ELF_2"))
    )
    (comp (ref "R127")
      (value "4.7k")
      (footprint "C0603_IPC_HD")
      (description "RES SMD 4.7K OHM 5% 1/10W 0603")
      (fields
        (field (name "MANUFACTURER") "Bourns Inc.")
        (field (name "MANUFACTURER PART NUMBER") "CR0603-JW-472ELF")
      )
      (libsource (lib "alfasat_lib_eps") (part "CR0603-JW-4.7kOm"))
    )
    (comp (ref "R128")
      (value "1 k")
      (footprint "R0603_IPC_HD")
      (description "1 kOhms ±1% 0.1W, 1/10W Chip Resistor 0603 (1608 Metric) Automotive AEC-Q200 Thick Film")
      (fields
        (field (name "MANUFACTURER") "Stackpole Electronics Inc")
        (field (name "MANUFACTURER PART NUMBER") "RMCF0603FT1K00")
      )
      (libsource (lib "alfasat_lib_eps") (part "CR0603-JW-1k_ISL92"))
    )
    (comp (ref "R129")
      (value "100k")
      (footprint "R0603_IPC_MD")
      (description "RES 100K OHM 1% 1/10W 0603")
      (fields
        (field (name "MANUFACTURER") "Stackpole Electronics Inc")
        (field (name "MANUFACTURER PART NUMBER") "RMCF0603FT100K")
      )
      (libsource (lib "alfasat_lib_eps") (part "CR0603-JW-104ELF"))
    )
    (comp (ref "R130")
      (value "100k")
      (footprint "R0603_IPC_MD")
      (description "RES 100K OHM 1% 1/10W 0603")
      (fields
        (field (name "MANUFACTURER") "Stackpole Electronics Inc")
        (field (name "MANUFACTURER PART NUMBER") "RMCF0603FT100K")
      )
      (libsource (lib "") (part "CR0603-JW-104ELF_1"))
    )
    (comp (ref "R131")
      (value "20mR")
      (footprint "alfasat_lib_eps:WSLP1206R002")
      (fields
        (field (name "MANUFACTURER") "Vishay Dale")
        (field (name "MANUFACTURER PART NUMBER") "WSLP1206R0200FEA")
      )
      (libsource (lib "alfasat_lib_eps") (part "WSLP1206R002"))
    )
    (comp (ref "R132")
      (value "2R")
      (footprint "alfasat_lib_eps:C0603_IPC_HD")
      (description "2 Ohms ±1% 0.125W, 1/8W Chip Resistor 0603 (1608 Metric) Automotive AEC-Q200 Thick Film")
      (fields
        (field (name "MANUFACTURER") "KOA Speer Electronics, Inc.")
        (field (name "MANUFACTURER PART NUMBER") "RK73H1JTTD2R00F")
      )
      (libsource (lib "alfasat_lib_eps") (part "CR0603-JW-2R"))
    )
    (comp (ref "R133")
      (value "2R")
      (footprint "alfasat_lib_eps:C0603_IPC_HD")
      (description "2 Ohms ±1% 0.125W, 1/8W Chip Resistor 0603 (1608 Metric) Automotive AEC-Q200 Thick Film")
      (fields
        (field (name "MANUFACTURER") "KOA Speer Electronics, Inc.")
        (field (name "MANUFACTURER PART NUMBER") "RK73H1JTTD2R00F")
      )
      (libsource (lib "alfasat_lib_eps") (part "CR0603-JW-2R"))
    )
    (comp (ref "R134")
      (value "0R")
      (footprint "R0603_IPC_MD")
      (description "RES SMD 0 OHM JUMPER 1/10W 0603")
      (fields
        (field (name "MANUFACTURER") "Bourns Inc.")
        (field (name "MANUFACTURER PART NUMBER") "CR0603-J/-000ELF")
      )
      (libsource (lib "alfasat_lib") (part "CR0603-J/-000ELF"))
    )
    (comp (ref "R135")
      (value "0R")
      (footprint "R0603_IPC_MD")
      (description "RES SMD 0 OHM JUMPER 1/10W 0603")
      (fields
        (field (name "MANUFACTURER") "Bourns Inc.")
        (field (name "MANUFACTURER PART NUMBER") "CR0603-J/-000ELF")
      )
      (libsource (lib "") (part "CR0603-J/-000ELF_2"))
    )
    (comp (ref "R136")
      (value "95.3k")
      (footprint "C0603_IPC_HD")
      (description "RES 95.3K OHM 1% 1/10W 0603")
      (fields
        (field (name "MANUFACTURER") "Stackpole Electronics Inc")
        (field (name "MANUFACTURER PART NUMBER") "RMCF0603FT95K3")
      )
      (libsource (lib "alfasat_lib_eps") (part "CR0603-JW-95.3k"))
    )
    (comp (ref "R137")
      (value "100k")
      (footprint "R0603_IPC_MD")
      (description "RES 100K OHM 1% 1/10W 0603")
      (fields
        (field (name "MANUFACTURER") "Stackpole Electronics Inc")
        (field (name "MANUFACTURER PART NUMBER") "RMCF0603FT100K")
      )
      (libsource (lib "") (part "CR0603-JW-104ELF_3"))
    )
    (comp (ref "R138")
      (value "158k")
      (footprint "R0603_IPC_HD")
      (description "58K ±1% 1/10W ±100ppm/℃ 0603")
      (fields
        (field (name "MANUFACTURER") "PANASONIC")
        (field (name "MANUFACTURER PART NUMBER") "ERJ3EKF1583V")
      )
      (libsource (lib "alfasat_lib_eps") (part "CR0603-JW-158k"))
    )
    (comp (ref "R139")
      (value "100k")
      (footprint "R0603_IPC_MD")
      (description "RES 100K OHM 1% 1/10W 0603")
      (fields
        (field (name "MANUFACTURER") "Stackpole Electronics Inc")
        (field (name "MANUFACTURER PART NUMBER") "RMCF0603FT100K")
      )
      (libsource (lib "") (part "CR0603-JW-104ELF_2"))
    )
    (comp (ref "R140")
      (value "1 k")
      (footprint "R0603_IPC_HD")
      (description "1 kOhms ±1% 0.1W, 1/10W Chip Resistor 0603 (1608 Metric) Automotive AEC-Q200 Thick Film")
      (fields
        (field (name "MANUFACTURER") "Stackpole Electronics Inc")
        (field (name "MANUFACTURER PART NUMBER") "RMCF0603FT1K00")
      )
      (libsource (lib "alfasat_lib_eps") (part "CR0603-JW-1k_ISL92"))
    )
    (comp (ref "R141")
      (value "100k")
      (footprint "R0603_IPC_MD")
      (description "RES 100K OHM 1% 1/10W 0603")
      (fields
        (field (name "MANUFACTURER") "Stackpole Electronics Inc")
        (field (name "MANUFACTURER PART NUMBER") "RMCF0603FT100K")
      )
      (libsource (lib "alfasat_lib_eps") (part "CR0603-JW-104ELF"))
    )
    (comp (ref "TP7")
      (value "TPS22975DSGR")
      (footprint "SON127P600-TPS22975")
      (description "IC LOAD SWITCH N-CH 6A")
      (fields (field (name "MANUFACTURER") "Texas Instruments"))
      (libsource (lib "alfasat_lib_eps") (part "TPS22975"))
    )
    (comp (ref "TP8")
      (value "TPS22810DBVR")
      (footprint "TPS22810DBVR_SOT95P280X145-6N")
      (description "Power Switch/Driver 1:1 N-Channel 2A SOT-23-6")
      (fields (field (name "MANUFACTURER") "Texas Instruments"))
      (libsource (lib "alfasat_lib_eps") (part "TPS22810DBVR"))
    )
    (comp (ref "TP9")
      (value "TPS22975DSGR")
      (footprint "SON127P600-TPS22975")
      (description "IC LOAD SWITCH N-CH 6A")
      (fields (field (name "MANUFACTURER") "Texas Instruments"))
      (libsource (lib "alfasat_lib_eps") (part "TPS22975"))
    )
    (comp (ref "TP10")
      (value "TPS22975DSGR")
      (footprint "SON127P600-TPS22975")
      (description "IC LOAD SWITCH N-CH 6A")
      (fields (field (name "MANUFACTURER") "Texas Instruments"))
      (libsource (lib "alfasat_lib_eps") (part "TPS22975"))
    )
    (comp (ref "TP11")
      (value "TPS22975DSGR")
      (footprint "SON127P600-TPS22975")
      (description "IC LOAD SWITCH N-CH 6A")
      (fields (field (name "MANUFACTURER") "Texas Instruments"))
      (libsource (lib "alfasat_lib_eps") (part "TPS22975"))
    )
    (comp (ref "U5")
      (value "INA381A3IDSGR")
      (footprint "SON127P600-8N(INA381)")
      (description "Current Sense Regulator High/Low-Side  8-WSON (2x2)")
      (fields (field (name "MANUFACTURER") "Texas Instruments"))
      (libsource (lib "alfasat_lib_eps") (part "INA381A3IDSGR"))
    )
    (comp (ref "U6")
      (value "TPS259540DSGT")
      (footprint "SON127P600-8N_TPS259540DSGT")
      (description "IC PWR MGMT EFUSE 2.7-18V 8WSON")
      (fields (field (name "MANUFACTURER") "Texas Instruments"))
      (libsource (lib "alfasat_lib_eps") (part "TPS259540DSGT"))
    )
    (comp (ref "U7")
      (value "INA381A3IDSGR")
      (footprint "SON127P600-8N(INA381)")
      (description "Current Sense Regulator High/Low-Side  8-WSON (2x2)")
      (fields (field (name "MANUFACTURER") "Texas Instruments"))
      (libsource (lib "alfasat_lib_eps") (part "INA381A3IDSGR"))
    )
    (comp (ref "U8")
      (value "TPS259540DSGT")
      (footprint "SON127P600-8N_TPS259540DSGT")
      (description "IC PWR MGMT EFUSE 2.7-18V 8WSON")
      (fields (field (name "MANUFACTURER") "Texas Instruments"))
      (libsource (lib "alfasat_lib_eps") (part "TPS259540DSGT"))
    )
    (comp (ref "U9")
      (value "INA381A3IDSGR")
      (footprint "SON127P600-8N(INA381)")
      (description "Current Sense Regulator High/Low-Side  8-WSON (2x2)")
      (fields (field (name "MANUFACTURER") "Texas Instruments"))
      (libsource (lib "alfasat_lib_eps") (part "INA381A3IDSGR"))
    )
    (comp (ref "U10")
      (value "TPS259540DSGT")
      (footprint "SON127P600-8N_TPS259540DSGT")
      (description "IC PWR MGMT EFUSE 2.7-18V 8WSON")
      (fields (field (name "MANUFACTURER") "Texas Instruments"))
      (libsource (lib "alfasat_lib_eps") (part "TPS259540DSGT"))
    )
    (comp (ref "U11")
      (value "INA381A3IDSGR")
      (footprint "SON127P600-8N(INA381)")
      (description "Current Sense Regulator High/Low-Side  8-WSON (2x2)")
      (fields (field (name "MANUFACTURER") "Texas Instruments"))
      (libsource (lib "alfasat_lib_eps") (part "INA381A3IDSGR"))
    )
    (comp (ref "U12")
      (value "INA381A3IDSGR")
      (footprint "SON127P600-8N(INA381)")
      (description "Current Sense Regulator High/Low-Side  8-WSON (2x2)")
      (fields (field (name "MANUFACTURER") "Texas Instruments"))
      (libsource (lib "alfasat_lib_eps") (part "INA381A3IDSGR"))
    )
  )
  (nets
    (net (code "1") (name "/CS_CH1") (class "Default")
      (node (ref "C74") (pin "2") (pinfunction "2_2") (pintype "passive"))
      (node (ref "R75") (pin "1") (pinfunction "1_1") (pintype "passive"))
      (node (ref "U5") (pin "7") (pinfunction "Vout_7") (pintype "passive"))
    )
    (net (code "2") (name "/CS_CH2") (class "Default")
      (node (ref "C87") (pin "2") (pinfunction "2_2") (pintype "passive"))
      (node (ref "R92") (pin "1") (pinfunction "1_1") (pintype "passive"))
      (node (ref "U7") (pin "7") (pinfunction "Vout_7") (pintype "passive"))
    )
    (net (code "3") (name "/CS_CH3") (class "Default")
      (node (ref "C97") (pin "2") (pinfunction "2_2") (pintype "passive"))
      (node (ref "R108") (pin "2") (pinfunction "2_2") (pintype "passive"))
      (node (ref "U9") (pin "7") (pinfunction "Vout_7") (pintype "passive"))
    )
    (net (code "4") (name "/CS_CH4") (class "Default")
      (node (ref "C107") (pin "2") (pinfunction "2_2") (pintype "passive"))
      (node (ref "R121") (pin "2") (pinfunction "2_2") (pintype "passive"))
      (node (ref "U11") (pin "7") (pinfunction "Vout_7") (pintype "passive"))
    )
    (net (code "5") (name "/CS_CH5") (class "Default")
      (node (ref "C115") (pin "2") (pinfunction "2_2") (pintype "passive"))
      (node (ref "R135") (pin "2") (pinfunction "2_2") (pintype "passive"))
      (node (ref "U12") (pin "7") (pinfunction "Vout_7") (pintype "passive"))
    )
    (net (code "6") (name "/FAULT_3V3") (class "Default")
      (node (ref "R87") (pin "1") (pinfunction "1_1") (pintype "passive"))
      (node (ref "U6") (pin "6") (pinfunction "~{FLT}_6") (pintype "passive"))
    )
    (net (code "7") (name "/FAULT_5V") (class "Default")
      (node (ref "R107") (pin "1") (pinfunction "1_1") (pintype "passive"))
      (node (ref "U8") (pin "6") (pinfunction "~{FLT}_6") (pintype "passive"))
    )
    (net (code "8") (name "/FAULT_7V4") (class "Default")
      (node (ref "R130") (pin "1") (pinfunction "1_1") (pintype "passive"))
      (node (ref "U10") (pin "6") (pinfunction "~{FLT}_6") (pintype "passive"))
    )
    (net (code "9") (name "/FAULT_CH1") (class "Default")
      (node (ref "C73") (pin "2") (pinfunction "2_2") (pintype "passive"))
      (node (ref "R74") (pin "2") (pinfunction "2_2") (pintype "passive"))
      (node (ref "R76") (pin "2") (pinfunction "2_2") (pintype "passive"))
      (node (ref "TP7") (pin "3") (pinfunction "ON_3") (pintype "passive"))
      (node (ref "U5") (pin "3") (pinfunction "~{ALERT}_3") (pintype "passive"))
    )
    (net (code "10") (name "/FAULT_CH2") (class "Default")
      (node (ref "C85") (pin "2") (pinfunction "2_2") (pintype "passive"))
      (node (ref "R91") (pin "2") (pinfunction "2_2") (pintype "passive"))
      (node (ref "R94") (pin "1") (pinfunction "1_1") (pintype "passive"))
      (node (ref "TP8") (pin "3") (pinfunction "EN_3") (pintype "passive"))
      (node (ref "U7") (pin "3") (pinfunction "~{ALERT}_3") (pintype "passive"))
    )
    (net (code "11") (name "/FAULT_CH3") (class "Default")
      (node (ref "C96") (pin "2") (pinfunction "2_2") (pintype "passive"))
      (node (ref "R106") (pin "2") (pinfunction "2_2") (pintype "passive"))
      (node (ref "R110") (pin "1") (pinfunction "1_1") (pintype "passive"))
      (node (ref "TP9") (pin "3") (pinfunction "ON_3") (pintype "passive"))
      (node (ref "U9") (pin "3") (pinfunction "~{ALERT}_3") (pintype "passive"))
    )
    (net (code "12") (name "/FAULT_CH4") (class "Default")
      (node (ref "C106") (pin "2") (pinfunction "2_2") (pintype "passive"))
      (node (ref "R119") (pin "2") (pinfunction "2_2") (pintype "passive"))
      (node (ref "R123") (pin "1") (pinfunction "1_1") (pintype "passive"))
      (node (ref "TP10") (pin "3") (pinfunction "ON_3") (pintype "passive"))
      (node (ref "U11") (pin "3") (pinfunction "~{ALERT}_3") (pintype "passive"))
    )
    (net (code "13") (name "/FAULT_CH5") (class "Default")
      (node (ref "C116") (pin "2") (pinfunction "2_2") (pintype "passive"))
      (node (ref "R134") (pin "2") (pinfunction "2_2") (pintype "passive"))
      (node (ref "R137") (pin "1") (pinfunction "1_1") (pintype "passive"))
      (node (ref "TP11") (pin "3") (pinfunction "ON_3") (pintype "passive"))
      (node (ref "U12") (pin "3") (pinfunction "~{ALERT}_3") (pintype "passive"))
    )
    (net (code "14") (name "/Load_EN_3V3") (class "Default")
      (node (ref "R82") (pin "2") (pinfunction "2_2") (pintype "passive"))
      (node (ref "R83") (pin "1") (pinfunction "1_1") (pintype "passive"))
      (node (ref "U6") (pin "2") (pinfunction "~{EN}/UVLO_2") (pintype "passive"))
    )
    (net (code "15") (name "/Load_EN_5V") (class "Default")
      (node (ref "R84") (pin "1") (pinfunction "1_1") (pintype "passive"))
      (node (ref "R99") (pin "2") (pinfunction "2_2") (pintype "passive"))
      (node (ref "U8") (pin "2") (pinfunction "~{EN}/UVLO_2") (pintype "passive"))
    )
    (net (code "16") (name "/Load_EN_7V4") (class "Default")
      (node (ref "R101") (pin "1") (pinfunction "1_1") (pintype "passive"))
      (node (ref "R105") (pin "2") (pinfunction "2_2") (pintype "passive"))
      (node (ref "U10") (pin "2") (pinfunction "~{EN}/UVLO_2") (pintype "passive"))
    )
    (net (code "17") (name "/Load_EN_CH1") (class "Default")
      (node (ref "R76") (pin "1") (pinfunction "1_1") (pintype "passive"))
    )
    (net (code "18") (name "/Load_EN_CH2") (class "Default")
      (node (ref "R94") (pin "2") (pinfunction "2_2") (pintype "passive"))
    )
    (net (code "19") (name "/Load_EN_CH3") (class "Default")
      (node (ref "R110") (pin "2") (pinfunction "2_2") (pintype "passive"))
    )
    (net (code "20") (name "/Load_EN_CH4") (class "Default")
      (node (ref "R123") (pin "2") (pinfunction "2_2") (pintype "passive"))
    )
    (net (code "21") (name "/Load_EN_CH5") (class "Default")
      (node (ref "R137") (pin "2") (pinfunction "2_2") (pintype "passive"))
    )
    (net (code "22") (name "/~{RES}1") (class "Default")
      (node (ref "R79") (pin "2") (pinfunction "2_2") (pintype "passive"))
    )
    (net (code "23") (name "/~{RES}2") (class "Default")
      (node (ref "R97") (pin "2") (pinfunction "2_2") (pintype "passive"))
    )
    (net (code "24") (name "/~{RES}3") (class "Default")
      (node (ref "R112") (pin "2") (pinfunction "2_2") (pintype "passive"))
    )
    (net (code "25") (name "/~{RES}4") (class "Default")
      (node (ref "R128") (pin "2") (pinfunction "2_2") (pintype "passive"))
    )
    (net (code "26") (name "/~{RES}5") (class "Default")
      (node (ref "R140") (pin "2") (pinfunction "2_2") (pintype "passive"))
    )
    (net (code "27") (name "3V3") (class "Default")
      (node (ref "C110") (pin "2") (pinfunction "2_2") (pintype "passive"))
      (node (ref "C112") (pin "2") (pinfunction "2_2") (pintype "passive"))
      (node (ref "C118") (pin "2") (pinfunction "2_2") (pintype "passive"))
      (node (ref "C79") (pin "1") (pinfunction "1_1") (pintype "passive"))
      (node (ref "C88") (pin "2") (pinfunction "2_2") (pintype "passive"))
      (node (ref "C99") (pin "2") (pinfunction "2_2") (pintype "passive"))
      (node (ref "R100") (pin "1") (pinfunction "1_1") (pintype "passive"))
      (node (ref "R102") (pin "2") (pinfunction "2_2") (pintype "passive"))
      (node (ref "R106") (pin "1") (pinfunction "1_1") (pintype "passive"))
      (node (ref "R107") (pin "2") (pinfunction "2_2") (pintype "passive"))
      (node (ref "R109") (pin "1") (pinfunction "1_1") (pintype "passive"))
      (node (ref "R111") (pin "2") (pinfunction "2_2") (pintype "passive"))
      (node (ref "R115") (pin "1") (pinfunction "1_1") (pintype "passive"))
      (node (ref "R116") (pin "2") (pinfunction "2_2") (pintype "passive"))
      (node (ref "R119") (pin "1") (pinfunction "1_1") (pintype "passive"))
      (node (ref "R122") (pin "1") (pinfunction "1_1") (pintype "passive"))
      (node (ref "R126") (pin "2") (pinfunction "2_2") (pintype "passive"))
      (node (ref "R130") (pin "2") (pinfunction "2_2") (pintype "passive"))
      (node (ref "R134") (pin "1") (pinfunction "1_1") (pintype "passive"))
      (node (ref "R136") (pin "2") (pinfunction "2_2") (pintype "passive"))
      (node (ref "R139") (pin "2") (pinfunction "2_2") (pintype "passive"))
      (node (ref "R74") (pin "1") (pinfunction "1_1") (pintype "passive"))
      (node (ref "R77") (pin "2") (pinfunction "2_2") (pintype "passive"))
      (node (ref "R78") (pin "1") (pinfunction "1_1") (pintype "passive"))
      (node (ref "R83") (pin "2") (pinfunction "2_2") (pintype "passive"))
      (node (ref "R87") (pin "2") (pinfunction "2_2") (pintype "passive"))
      (node (ref "R91") (pin "1") (pinfunction "1_1") (pintype "passive"))
      (node (ref "R93") (pin "2") (pinfunction "2_2") (pintype "passive"))
      (node (ref "R96") (pin "2") (pinfunction "2_2") (pintype "passive"))
      (node (ref "U11") (pin "2") (pinfunction "VS+_2") (pintype "passive"))
      (node (ref "U12") (pin "2") (pinfunction "VS+_2") (pintype "passive"))
      (node (ref "U5") (pin "2") (pinfunction "VS+_2") (pintype "passive"))
      (node (ref "U6") (pin "3") (pinfunction "IN_3") (pintype "passive"))
      (node (ref "U6") (pin "4") (pinfunction "IN_4") (pintype "passive"))
      (node (ref "U7") (pin "2") (pinfunction "VS+_2") (pintype "passive"))
      (node (ref "U9") (pin "2") (pinfunction "VS+_2") (pintype "passive"))
    )
    (net (code "28") (name "3V3_CH3") (class "Default")
      (node (ref "C95") (pin "2") (pinfunction "2_2") (pintype "passive"))
      (node (ref "TP9") (pin "7") (pinfunction "VOUT_7") (pintype "passive"))
      (node (ref "TP9") (pin "8") (pinfunction "VOUT_8") (pintype "passive"))
    )
    (net (code "29") (name "3V3_CH4") (class "Default")
      (node (ref "C105") (pin "2") (pinfunction "2_2") (pintype "passive"))
      (node (ref "TP10") (pin "7") (pinfunction "VOUT_7") (pintype "passive"))
      (node (ref "TP10") (pin "8") (pinfunction "VOUT_8") (pintype "passive"))
    )
    (net (code "30") (name "3V3_LINE") (class "Default")
      (node (ref "C91") (pin "2") (pinfunction "2_2") (pintype "passive"))
      (node (ref "U6") (pin "5") (pinfunction "OUT_5") (pintype "passive"))
    )
    (net (code "31") (name "5V") (class "Default")
      (node (ref "C108") (pin "2") (pinfunction "2_2") (pintype "passive"))
      (node (ref "C117") (pin "2") (pinfunction "2_2") (pintype "passive"))
      (node (ref "C75") (pin "2") (pinfunction "2_2") (pintype "passive"))
      (node (ref "C77") (pin "2") (pinfunction "2_2") (pintype "passive"))
      (node (ref "C98") (pin "2") (pinfunction "2_2") (pintype "passive"))
      (node (ref "R131") (pin "1") (pinfunction "1_1") (pintype "passive"))
      (node (ref "R132") (pin "2") (pinfunction "2_2") (pintype "passive"))
      (node (ref "R71") (pin "1") (pinfunction "1_1") (pintype "passive"))
      (node (ref "R72") (pin "2") (pinfunction "2_2") (pintype "passive"))
      (node (ref "R84") (pin "2") (pinfunction "2_2") (pintype "passive"))
      (node (ref "TP10") (pin "4") (pinfunction "Vbias_4") (pintype "passive"))
      (node (ref "TP11") (pin "4") (pinfunction "Vbias_4") (pintype "passive"))
      (node (ref "TP7") (pin "4") (pinfunction "Vbias_4") (pintype "passive"))
      (node (ref "TP9") (pin "4") (pinfunction "Vbias_4") (pintype "passive"))
      (node (ref "U8") (pin "3") (pinfunction "IN_3") (pintype "passive"))
      (node (ref "U8") (pin "4") (pinfunction "IN_4") (pintype "passive"))
    )
    (net (code "32") (name "5V_CH1") (class "Default")
      (node (ref "C72") (pin "2") (pinfunction "2_2") (pintype "passive"))
      (node (ref "TP7") (pin "7") (pinfunction "VOUT_7") (pintype "passive"))
      (node (ref "TP7") (pin "8") (pinfunction "VOUT_8") (pintype "passive"))
    )
    (net (code "33") (name "5V_CH5") (class "Default")
      (node (ref "C114") (pin "2") (pinfunction "2_2") (pintype "passive"))
      (node (ref "TP11") (pin "7") (pinfunction "VOUT_7") (pintype "passive"))
      (node (ref "TP11") (pin "8") (pinfunction "VOUT_8") (pintype "passive"))
    )
    (net (code "34") (name "5V_LINE") (class "Default")
      (node (ref "C90") (pin "2") (pinfunction "2_2") (pintype "passive"))
      (node (ref "U8") (pin "5") (pinfunction "OUT_5") (pintype "passive"))
    )
    (net (code "35") (name "7V4") (class "Default")
      (node (ref "C102") (pin "2") (pinfunction "2_2") (pintype "passive"))
      (node (ref "U10") (pin "5") (pinfunction "OUT_5") (pintype "passive"))
    )
    (net (code "36") (name "7V4_CH2") (class "Default")
      (node (ref "C83") (pin "2") (pinfunction "2_2") (pintype "passive"))
      (node (ref "C84") (pin "2") (pinfunction "2_2") (pintype "passive"))
      (node (ref "R90") (pin "1") (pinfunction "1_1") (pintype "passive"))
      (node (ref "TP8") (pin "6") (pinfunction "Vout_6") (pintype "passive"))
    )
    (net (code "37") (name "GND") (class "Default")
      (node (ref "C100") (pin "1") (pinfunction "1_1") (pintype "passive"))
      (node (ref "C102") (pin "1") (pinfunction "1_1") (pintype "passive"))
      (node (ref "C104") (pin "1") (pinfunction "1_1") (pintype "passive"))
      (node (ref "C105") (pin "1") (pinfunction "1_1") (pintype "passive"))
      (node (ref "C106") (pin "1") (pinfunction "1_1") (pintype "passive"))
      (node (ref "C107") (pin "1") (pinfunction "1_1") (pintype "passive"))
      (node (ref "C108") (pin "1") (pinfunction "1_1") (pintype "passive"))
      (node (ref "C109") (pin "2") (pinfunction "2_2") (pintype "passive"))
      (node (ref "C110") (pin "1") (pinfunction "1_1") (pintype "passive"))
      (node (ref "C111") (pin "1") (pinfunction "1_1") (pintype "passive"))
      (node (ref "C112") (pin "1") (pinfunction "1_1") (pintype "passive"))
      (node (ref "C113") (pin "1") (pinfunction "1_1") (pintype "passive"))
      (node (ref "C114") (pin "1") (pinfunction "1_1") (pintype "passive"))
      (node (ref "C115") (pin "1") (pinfunction "1_1") (pintype "passive"))
      (node (ref "C116") (pin "1") (pinfunction "1_1") (pintype "passive"))
      (node (ref "C117") (pin "1") (pinfunction "1_1") (pintype "passive"))
      (node (ref "C118") (pin "1") (pinfunction "1_1") (pintype "passive"))
      (node (ref "C69") (pin "1") (pinfunction "1_1") (pintype "passive"))
      (node (ref "C71") (pin "1") (pinfunction "1_1") (pintype "passive"))
      (node (ref "C72") (pin "1") (pinfunction "1_1") (pintype "passive"))
      (node (ref "C73") (pin "1") (pinfunction "1_1") (pintype "passive"))
      (node (ref "C74") (pin "1") (pinfunction "1_1") (pintype "passive"))
      (node (ref "C75") (pin "1") (pinfunction "1_1") (pintype "passive"))
      (node (ref "C76") (pin "1") (pinfunction "1_1") (pintype "passive"))
      (node (ref "C77") (pin "1") (pinfunction "1_1") (pintype "passive"))
      (node (ref "C78") (pin "1") (pinfunction "1_1") (pintype "passive"))
      (node (ref "C79") (pin "2") (pinfunction "2_2") (pintype "passive"))
      (node (ref "C80") (pin "2") (pinfunction "2_2") (pintype "passive"))
      (node (ref "C81") (pin "1") (pinfunction "1_1") (pintype "passive"))
      (node (ref "C83") (pin "1") (pinfunction "1_1") (pintype "passive"))
      (node (ref "C84") (pin "1") (pinfunction "1_1") (pintype "passive"))
      (node (ref "C85") (pin "1") (pinfunction "1_1") (pintype "passive"))
      (node (ref "C86") (pin "1") (pinfunction "1_1") (pintype "passive"))
      (node (ref "C87") (pin "1") (pinfunction "1_1") (pintype "passive"))
      (node (ref "C88") (pin "1") (pinfunction "1_1") (pintype "passive"))
      (node (ref "C89") (pin "1") (pinfunction "1_1") (pintype "passive"))
      (node (ref "C90") (pin "1") (pinfunction "1_1") (pintype "passive"))
      (node (ref "C91") (pin "1") (pinfunction "1_1") (pintype "passive"))
      (node (ref "C93") (pin "2") (pinfunction "2_2") (pintype "passive"))
      (node (ref "C94") (pin "1") (pinfunction "1_1") (pintype "passive"))
      (node (ref "C95") (pin "1") (pinfunction "1_1") (pintype "passive"))
      (node (ref "C96") (pin "1") (pinfunction "1_1") (pintype "passive"))
      (node (ref "C97") (pin "1") (pinfunction "1_1") (pintype "passive"))
      (node (ref "C98") (pin "1") (pinfunction "1_1") (pintype "passive"))
      (node (ref "C99") (pin "1") (pinfunction "1_1") (pintype "passive"))
      (node (ref "Q11") (pin "2") (pinfunction "S_2") (pintype "passive"))
      (node (ref "Q13") (pin "2") (pinfunction "S_2") (pintype "passive"))
      (node (ref "Q15") (pin "2") (pinfunction "S_2") (pintype "passive"))
      (node (ref "Q17") (pin "2") (pinfunction "S_2") (pintype "passive"))
      (node (ref "Q18") (pin "2") (pinfunction "S_2") (pintype "passive"))
      (node (ref "R104") (pin "1") (pinfunction "1_1") (pintype "passive"))
      (node (ref "R105") (pin "1") (pinfunction "1_1") (pintype "passive"))
      (node (ref "R113") (pin "1") (pinfunction "1_1") (pintype "passive"))
      (node (ref "R114") (pin "1") (pinfunction "1_1") (pintype "passive"))
      (node (ref "R127") (pin "1") (pinfunction "1_1") (pintype "passive"))
      (node (ref "R129") (pin "1") (pinfunction "1_1") (pintype "passive"))
      (node (ref "R138") (pin "1") (pinfunction "1_1") (pintype "passive"))
      (node (ref "R141") (pin "1") (pinfunction "1_1") (pintype "passive"))
      (node (ref "R33") (pin "1") (pinfunction "1_1") (pintype "passive"))
      (node (ref "R80") (pin "1") (pinfunction "1_1") (pintype "passive"))
      (node (ref "R81") (pin "2") (pinfunction "2_2") (pintype "passive"))
      (node (ref "R82") (pin "1") (pinfunction "1_1") (pintype "passive"))
      (node (ref "R85") (pin "1") (pinfunction "1_1") (pintype "passive"))
      (node (ref "R95") (pin "1") (pinfunction "1_1") (pintype "passive"))
      (node (ref "R98") (pin "1") (pinfunction "1_1") (pintype "passive"))
      (node (ref "R99") (pin "1") (pinfunction "1_1") (pintype "passive"))
      (node (ref "TP10") (pin "5") (pinfunction "GND_5") (pintype "passive"))
      (node (ref "TP10") (pin "9") (pinfunction "PAD_9") (pintype "passive"))
      (node (ref "TP11") (pin "5") (pinfunction "GND_5") (pintype "passive"))
      (node (ref "TP11") (pin "9") (pinfunction "PAD_9") (pintype "passive"))
      (node (ref "TP7") (pin "5") (pinfunction "GND_5") (pintype "passive"))
      (node (ref "TP7") (pin "9") (pinfunction "PAD_9") (pintype "passive"))
      (node (ref "TP8") (pin "2") (pinfunction "GND_2") (pintype "passive"))
      (node (ref "TP9") (pin "5") (pinfunction "GND_5") (pintype "passive"))
      (node (ref "TP9") (pin "9") (pinfunction "PAD_9") (pintype "passive"))
      (node (ref "U10") (pin "8") (pinfunction "GND_8") (pintype "passive"))
      (node (ref "U10") (pin "9") (pinfunction "PGND_9") (pintype "passive"))
      (node (ref "U11") (pin "0") (pinfunction "GND_0") (pintype "passive"))
      (node (ref "U12") (pin "0") (pinfunction "GND_0") (pintype "passive"))
      (node (ref "U5") (pin "0") (pinfunction "GND_0") (pintype "passive"))
      (node (ref "U6") (pin "8") (pinfunction "GND_8") (pintype "passive"))
      (node (ref "U6") (pin "9") (pinfunction "PGND_9") (pintype "passive"))
      (node (ref "U7") (pin "0") (pinfunction "GND_0") (pintype "passive"))
      (node (ref "U8") (pin "8") (pinfunction "GND_8") (pintype "passive"))
      (node (ref "U8") (pin "9") (pinfunction "PGND_9") (pintype "passive"))
      (node (ref "U9") (pin "0") (pinfunction "GND_0") (pintype "passive"))
    )
    (net (code "38") (name "Net-(C69-Pad2)") (class "Default")
      (node (ref "C69") (pin "2") (pinfunction "2_2") (pintype "passive"))
      (node (ref "R71") (pin "2") (pinfunction "2_2") (pintype "passive"))
      (node (ref "R73") (pin "2") (pinfunction "2_2") (pintype "passive"))
      (node (ref "TP7") (pin "1") (pinfunction "VIN_1") (pintype "passive"))
      (node (ref "TP7") (pin "2") (pinfunction "VIN_2") (pintype "passive"))
    )
    (net (code "39") (name "Net-(C89-Pad2)") (class "Default")
      (node (ref "C89") (pin "2") (pinfunction "2_2") (pintype "passive"))
      (node (ref "R100") (pin "2") (pinfunction "2_2") (pintype "passive"))
      (node (ref "R103") (pin "2") (pinfunction "2_2") (pintype "passive"))
      (node (ref "TP9") (pin "1") (pinfunction "VIN_1") (pintype "passive"))
      (node (ref "TP9") (pin "2") (pinfunction "VIN_2") (pintype "passive"))
    )
    (net (code "40") (name "Net-(C100-Pad2)") (class "Default")
      (node (ref "C100") (pin "2") (pinfunction "2_2") (pintype "passive"))
      (node (ref "R115") (pin "2") (pinfunction "2_2") (pintype "passive"))
      (node (ref "R117") (pin "2") (pinfunction "2_2") (pintype "passive"))
      (node (ref "TP10") (pin "1") (pinfunction "VIN_1") (pintype "passive"))
      (node (ref "TP10") (pin "2") (pinfunction "VIN_2") (pintype "passive"))
    )
    (net (code "41") (name "Net-(C111-Pad2)") (class "Default")
      (node (ref "C111") (pin "2") (pinfunction "2_2") (pintype "passive"))
      (node (ref "R131") (pin "2") (pinfunction "2_2") (pintype "passive"))
      (node (ref "R133") (pin "2") (pinfunction "2_2") (pintype "passive"))
      (node (ref "TP11") (pin "1") (pinfunction "VIN_1") (pintype "passive"))
      (node (ref "TP11") (pin "2") (pinfunction "VIN_2") (pintype "passive"))
    )
    (net (code "42") (name "Net-(Q11-D)") (class "Default")
      (node (ref "Q11") (pin "3") (pinfunction "D_3") (pintype "passive"))
      (node (ref "R78") (pin "2") (pinfunction "2_2") (pintype "passive"))
      (node (ref "U5") (pin "4") (pinfunction "RESET_4") (pintype "passive"))
    )
    (net (code "43") (name "Net-(Q11-G)") (class "Default")
      (node (ref "Q11") (pin "1") (pinfunction "G_1") (pintype "passive"))
      (node (ref "R79") (pin "1") (pinfunction "1_1") (pintype "passive"))
      (node (ref "R81") (pin "1") (pinfunction "1_1") (pintype "passive"))
    )
    (net (code "44") (name "Net-(Q13-D)") (class "Default")
      (node (ref "Q13") (pin "3") (pinfunction "D_3") (pintype "passive"))
      (node (ref "R96") (pin "1") (pinfunction "1_1") (pintype "passive"))
      (node (ref "U7") (pin "4") (pinfunction "RESET_4") (pintype "passive"))
    )
    (net (code "45") (name "Net-(Q13-G)") (class "Default")
      (node (ref "Q13") (pin "1") (pinfunction "G_1") (pintype "passive"))
      (node (ref "R97") (pin "1") (pinfunction "1_1") (pintype "passive"))
      (node (ref "R98") (pin "2") (pinfunction "2_2") (pintype "passive"))
    )
    (net (code "46") (name "Net-(Q15-D)") (class "Default")
      (node (ref "Q15") (pin "3") (pinfunction "D_3") (pintype "passive"))
      (node (ref "R111") (pin "1") (pinfunction "1_1") (pintype "passive"))
      (node (ref "U9") (pin "4") (pinfunction "RESET_4") (pintype "passive"))
    )
    (net (code "47") (name "Net-(Q15-G)") (class "Default")
      (node (ref "Q15") (pin "1") (pinfunction "G_1") (pintype "passive"))
      (node (ref "R112") (pin "1") (pinfunction "1_1") (pintype "passive"))
      (node (ref "R114") (pin "2") (pinfunction "2_2") (pintype "passive"))
    )
    (net (code "48") (name "Net-(Q17-D)") (class "Default")
      (node (ref "Q17") (pin "3") (pinfunction "D_3") (pintype "passive"))
      (node (ref "R126") (pin "1") (pinfunction "1_1") (pintype "passive"))
      (node (ref "U11") (pin "4") (pinfunction "RESET_4") (pintype "passive"))
    )
    (net (code "49") (name "Net-(Q17-G)") (class "Default")
      (node (ref "Q17") (pin "1") (pinfunction "G_1") (pintype "passive"))
      (node (ref "R128") (pin "1") (pinfunction "1_1") (pintype "passive"))
      (node (ref "R129") (pin "2") (pinfunction "2_2") (pintype "passive"))
    )
    (net (code "50") (name "Net-(Q18-D)") (class "Default")
      (node (ref "Q18") (pin "3") (pinfunction "D_3") (pintype "passive"))
      (node (ref "R139") (pin "1") (pinfunction "1_1") (pintype "passive"))
      (node (ref "U12") (pin "4") (pinfunction "RESET_4") (pintype "passive"))
    )
    (net (code "51") (name "Net-(Q18-G)") (class "Default")
      (node (ref "Q18") (pin "1") (pinfunction "G_1") (pintype "passive"))
      (node (ref "R140") (pin "1") (pinfunction "1_1") (pintype "passive"))
      (node (ref "R141") (pin "2") (pinfunction "2_2") (pintype "passive"))
    )
    (net (code "52") (name "Net-(TP7-CT)") (class "Default")
      (node (ref "C71") (pin "2") (pinfunction "2_2") (pintype "passive"))
      (node (ref "TP7") (pin "6") (pinfunction "CT_6") (pintype "passive"))
    )
    (net (code "53") (name "Net-(TP8-CT)") (class "Default")
      (node (ref "C86") (pin "2") (pinfunction "2_2") (pintype "passive"))
      (node (ref "TP8") (pin "4") (pinfunction "CT_4") (pintype "passive"))
    )
    (net (code "54") (name "Net-(TP8-QOD)") (class "Default")
      (node (ref "R90") (pin "2") (pinfunction "2_2") (pintype "passive"))
      (node (ref "TP8") (pin "5") (pinfunction "QOD_5") (pintype "passive"))
    )
    (net (code "55") (name "Net-(TP8-Vin)") (class "Default")
      (node (ref "C81") (pin "2") (pinfunction "2_2") (pintype "passive"))
      (node (ref "R86") (pin "2") (pinfunction "2_2") (pintype "passive"))
      (node (ref "R89") (pin "2") (pinfunction "2_2") (pintype "passive"))
      (node (ref "TP8") (pin "1") (pinfunction "Vin_1") (pintype "passive"))
    )
    (net (code "56") (name "Net-(TP9-CT)") (class "Default")
      (node (ref "C94") (pin "2") (pinfunction "2_2") (pintype "passive"))
      (node (ref "TP9") (pin "6") (pinfunction "CT_6") (pintype "passive"))
    )
    (net (code "57") (name "Net-(TP10-CT)") (class "Default")
      (node (ref "C104") (pin "2") (pinfunction "2_2") (pintype "passive"))
      (node (ref "TP10") (pin "6") (pinfunction "CT_6") (pintype "passive"))
    )
    (net (code "58") (name "Net-(TP11-CT)") (class "Default")
      (node (ref "C113") (pin "2") (pinfunction "2_2") (pintype "passive"))
      (node (ref "TP11") (pin "6") (pinfunction "CT_6") (pintype "passive"))
    )
    (net (code "59") (name "Net-(U5-CMPIN)") (class "Default")
      (node (ref "R75") (pin "2") (pinfunction "2_2") (pintype "passive"))
      (node (ref "U5") (pin "6") (pinfunction "CMPIN_6") (pintype "passive"))
    )
    (net (code "60") (name "Net-(U5-CMPREF)") (class "Default")
      (node (ref "C76") (pin "2") (pinfunction "2_2") (pintype "passive"))
      (node (ref "R77") (pin "1") (pinfunction "1_1") (pintype "passive"))
      (node (ref "R80") (pin "2") (pinfunction "2_2") (pintype "passive"))
      (node (ref "U5") (pin "5") (pinfunction "CMPREF_5") (pintype "passive"))
    )
    (net (code "61") (name "Net-(U5-IN+)") (class "Default")
      (node (ref "C70") (pin "1") (pinfunction "1_1") (pintype "passive"))
      (node (ref "R72") (pin "1") (pinfunction "1_1") (pintype "passive"))
      (node (ref "U5") (pin "1") (pinfunction "IN+_1") (pintype "passive"))
    )
    (net (code "62") (name "Net-(U5-IN-)") (class "Default")
      (node (ref "C70") (pin "2") (pinfunction "2_2") (pintype "passive"))
      (node (ref "R73") (pin "1") (pinfunction "1_1") (pintype "passive"))
      (node (ref "U5") (pin "8") (pinfunction "IN-_8") (pintype "passive"))
    )
    (net (code "63") (name "Net-(U6-ILM)") (class "Default")
      (node (ref "R33") (pin "2") (pinfunction "2_2") (pintype "passive"))
      (node (ref "U6") (pin "7") (pinfunction "ILM_7") (pintype "passive"))
    )
    (net (code "64") (name "Net-(U6-dVdt)") (class "Default")
      (node (ref "C80") (pin "1") (pinfunction "1_1") (pintype "passive"))
      (node (ref "U6") (pin "1") (pinfunction "dVdt_1") (pintype "passive"))
    )
    (net (code "65") (name "Net-(U7-CMPIN)") (class "Default")
      (node (ref "R92") (pin "2") (pinfunction "2_2") (pintype "passive"))
      (node (ref "U7") (pin "6") (pinfunction "CMPIN_6") (pintype "passive"))
    )
    (net (code "66") (name "Net-(U7-CMPREF)") (class "Default")
      (node (ref "R93") (pin "1") (pinfunction "1_1") (pintype "passive"))
      (node (ref "R95") (pin "2") (pinfunction "2_2") (pintype "passive"))
      (node (ref "U7") (pin "5") (pinfunction "CMPREF_5") (pintype "passive"))
    )
    (net (code "67") (name "Net-(U7-IN+)") (class "Default")
      (node (ref "C82") (pin "1") (pinfunction "1_1") (pintype "passive"))
      (node (ref "R88") (pin "1") (pinfunction "1_1") (pintype "passive"))
      (node (ref "U7") (pin "1") (pinfunction "IN+_1") (pintype "passive"))
    )
    (net (code "68") (name "Net-(U7-IN-)") (class "Default")
      (node (ref "C82") (pin "2") (pinfunction "2_2") (pintype "passive"))
      (node (ref "R89") (pin "1") (pinfunction "1_1") (pintype "passive"))
      (node (ref "U7") (pin "8") (pinfunction "IN-_8") (pintype "passive"))
    )
    (net (code "69") (name "Net-(U8-ILM)") (class "Default")
      (node (ref "R85") (pin "2") (pinfunction "2_2") (pintype "passive"))
      (node (ref "U8") (pin "7") (pinfunction "ILM_7") (pintype "passive"))
    )
    (net (code "70") (name "Net-(U8-dVdt)") (class "Default")
      (node (ref "C93") (pin "1") (pinfunction "1_1") (pintype "passive"))
      (node (ref "U8") (pin "1") (pinfunction "dVdt_1") (pintype "passive"))
    )
    (net (code "71") (name "Net-(U9-CMPIN)") (class "Default")
      (node (ref "R108") (pin "1") (pinfunction "1_1") (pintype "passive"))
      (node (ref "U9") (pin "6") (pinfunction "CMPIN_6") (pintype "passive"))
    )
    (net (code "72") (name "Net-(U9-CMPREF)") (class "Default")
      (node (ref "R109") (pin "2") (pinfunction "2_2") (pintype "passive"))
      (node (ref "R113") (pin "2") (pinfunction "2_2") (pintype "passive"))
      (node (ref "U9") (pin "5") (pinfunction "CMPREF_5") (pintype "passive"))
    )
    (net (code "73") (name "Net-(U9-IN+)") (class "Default")
      (node (ref "C92") (pin "1") (pinfunction "1_1") (pintype "passive"))
      (node (ref "R102") (pin "1") (pinfunction "1_1") (pintype "passive"))
      (node (ref "U9") (pin "1") (pinfunction "IN+_1") (pintype "passive"))
    )
    (net (code "74") (name "Net-(U9-IN-)") (class "Default")
      (node (ref "C92") (pin "2") (pinfunction "2_2") (pintype "passive"))
      (node (ref "R103") (pin "1") (pinfunction "1_1") (pintype "passive"))
      (node (ref "U9") (pin "8") (pinfunction "IN-_8") (pintype "passive"))
    )
    (net (code "75") (name "Net-(U10-ILM)") (class "Default")
      (node (ref "R104") (pin "2") (pinfunction "2_2") (pintype "passive"))
      (node (ref "U10") (pin "7") (pinfunction "ILM_7") (pintype "passive"))
    )
    (net (code "76") (name "Net-(U10-dVdt)") (class "Default")
      (node (ref "C109") (pin "1") (pinfunction "1_1") (pintype "passive"))
      (node (ref "U10") (pin "1") (pinfunction "dVdt_1") (pintype "passive"))
    )
    (net (code "77") (name "Net-(U11-CMPIN)") (class "Default")
      (node (ref "R121") (pin "1") (pinfunction "1_1") (pintype "passive"))
      (node (ref "U11") (pin "6") (pinfunction "CMPIN_6") (pintype "passive"))
    )
    (net (code "78") (name "Net-(U11-CMPREF)") (class "Default")
      (node (ref "R122") (pin "2") (pinfunction "2_2") (pintype "passive"))
      (node (ref "R127") (pin "2") (pinfunction "2_2") (pintype "passive"))
      (node (ref "U11") (pin "5") (pinfunction "CMPREF_5") (pintype "passive"))
    )
    (net (code "79") (name "Net-(U11-IN+)") (class "Default")
      (node (ref "C101") (pin "1") (pinfunction "1_1") (pintype "passive"))
      (node (ref "R116") (pin "1") (pinfunction "1_1") (pintype "passive"))
      (node (ref "U11") (pin "1") (pinfunction "IN+_1") (pintype "passive"))
    )
    (net (code "80") (name "Net-(U11-IN-)") (class "Default")
      (node (ref "C101") (pin "2") (pinfunction "2_2") (pintype "passive"))
      (node (ref "R117") (pin "1") (pinfunction "1_1") (pintype "passive"))
      (node (ref "U11") (pin "8") (pinfunction "IN-_8") (pintype "passive"))
    )
    (net (code "81") (name "Net-(U12-CMPIN)") (class "Default")
      (node (ref "R135") (pin "1") (pinfunction "1_1") (pintype "passive"))
      (node (ref "U12") (pin "6") (pinfunction "CMPIN_6") (pintype "passive"))
    )
    (net (code "82") (name "Net-(U12-CMPREF)") (class "Default")
      (node (ref "R136") (pin "1") (pinfunction "1_1") (pintype "passive"))
      (node (ref "R138") (pin "2") (pinfunction "2_2") (pintype "passive"))
      (node (ref "U12") (pin "5") (pinfunction "CMPREF_5") (pintype "passive"))
    )
    (net (code "83") (name "Net-(U12-IN+)") (class "Default")
      (node (ref "C103") (pin "1") (pinfunction "1_1") (pintype "passive"))
      (node (ref "R132") (pin "1") (pinfunction "1_1") (pintype "passive"))
      (node (ref "U12") (pin "1") (pinfunction "IN+_1") (pintype "passive"))
    )
    (net (code "84") (name "Net-(U12-IN-)") (class "Default")
      (node (ref "C103") (pin "2") (pinfunction "2_2") (pintype "passive"))
      (node (ref "R133") (pin "1") (pinfunction "1_1") (pintype "passive"))
      (node (ref "U12") (pin "8") (pinfunction "IN-_8") (pintype "passive"))
    )
    (net (code "85") (name "VSYS") (class "Default")
      (node (ref "C78") (pin "2") (pinfunction "2_2") (pintype "passive"))
      (node (ref "R101") (pin "2") (pinfunction "2_2") (pintype "passive"))
      (node (ref "R86") (pin "1") (pinfunction "1_1") (pintype "passive"))
      (node (ref "R88") (pin "2") (pinfunction "2_2") (pintype "passive"))
      (node (ref "U10") (pin "3") (pinfunction "IN_3") (pintype "passive"))
      (node (ref "U10") (pin "4") (pinfunction "IN_4") (pintype "passive"))
    )
  )
)
